# SVCSYNTH00.net
KiCad netlist of a schematic drawn in EAGLE
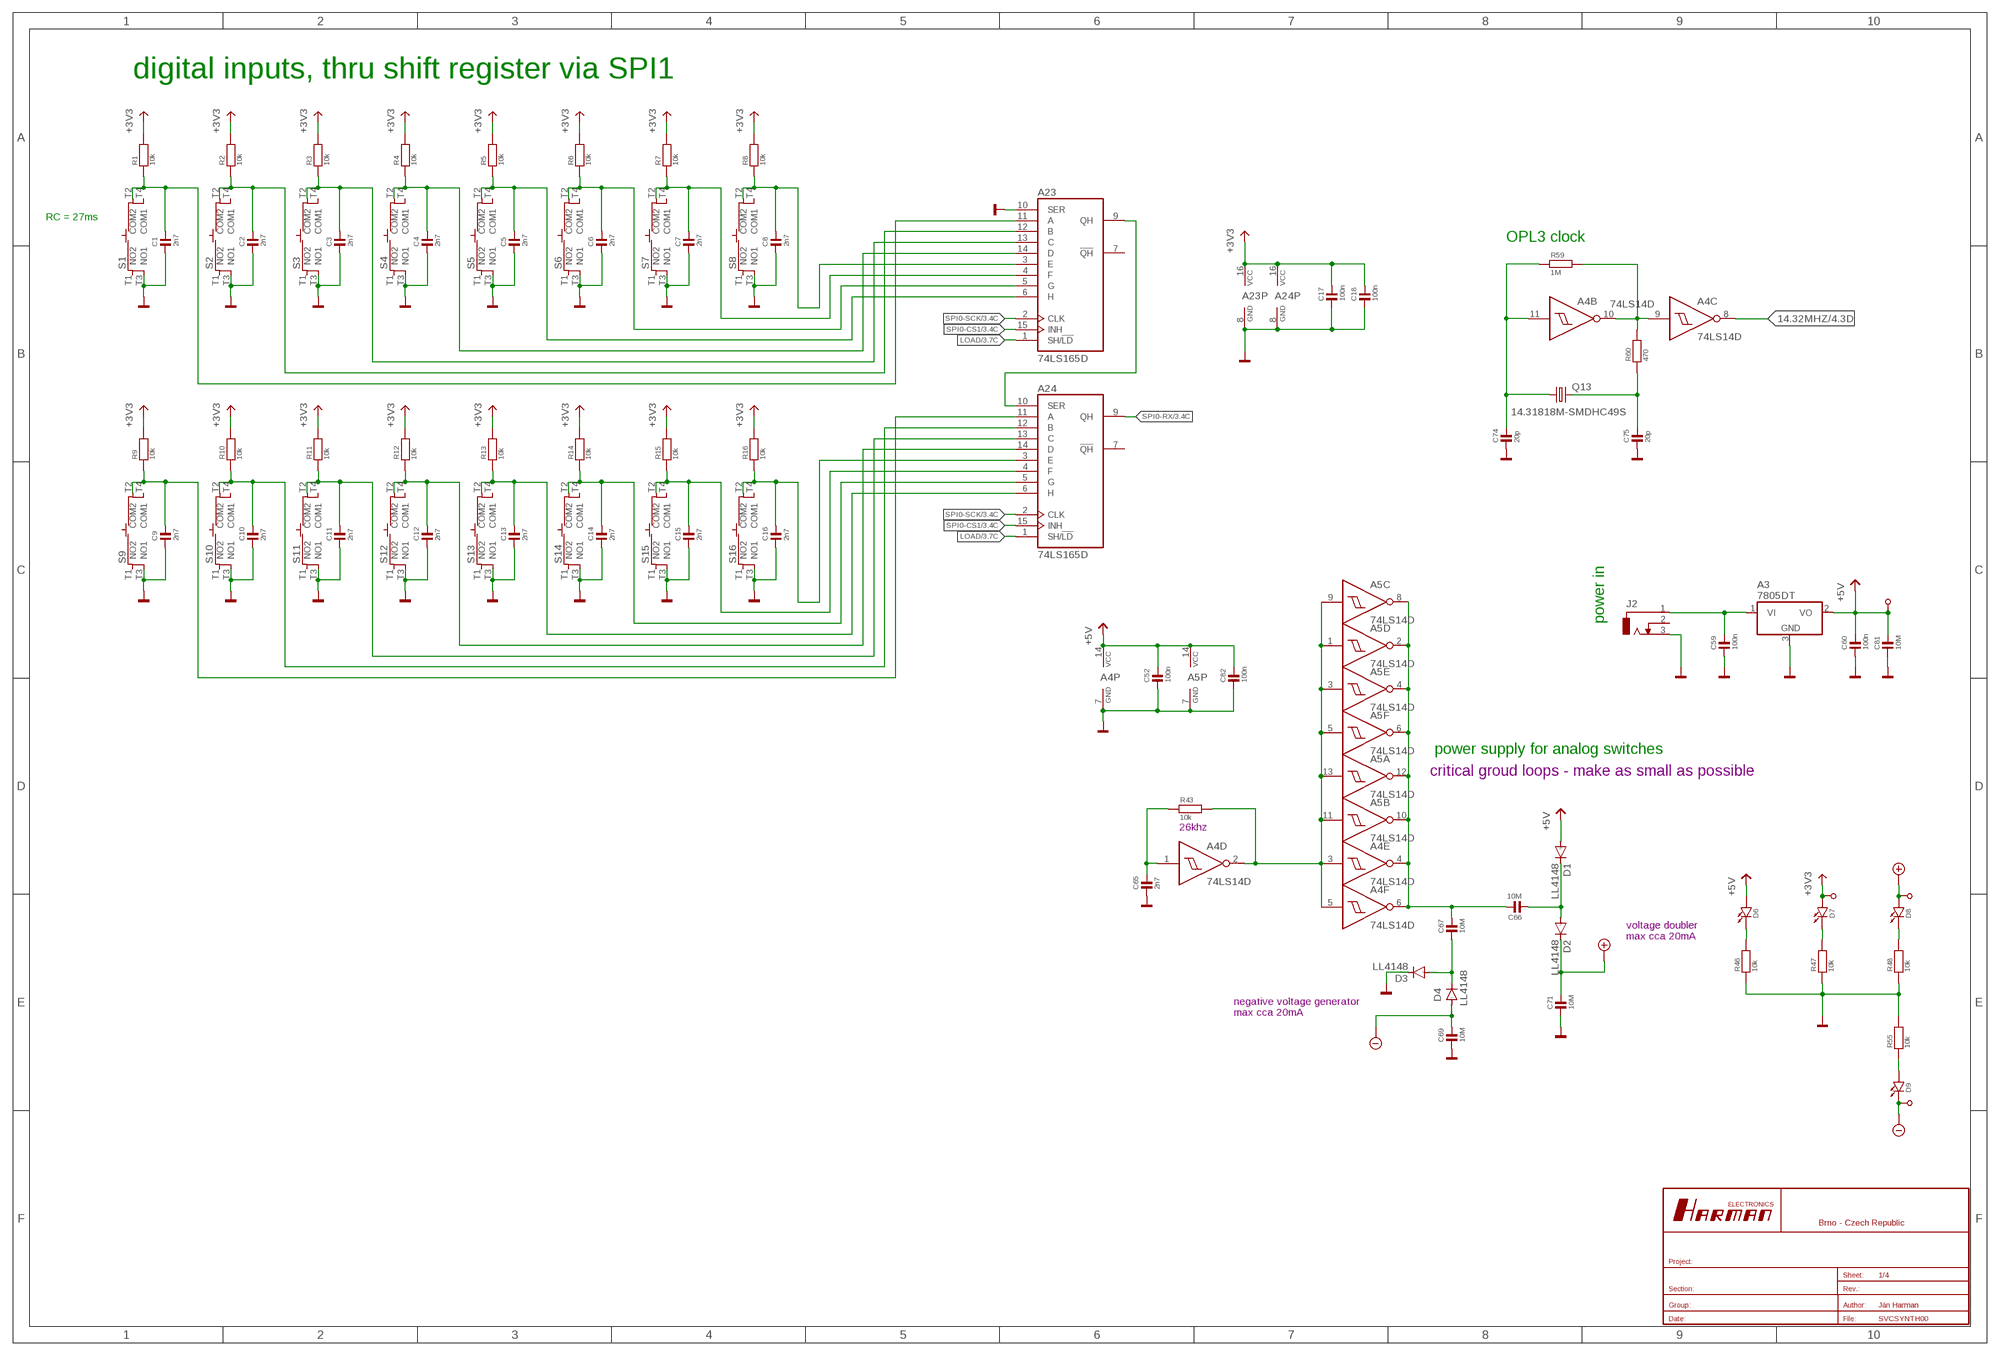
[diagram p0: schematic, sheet 1]
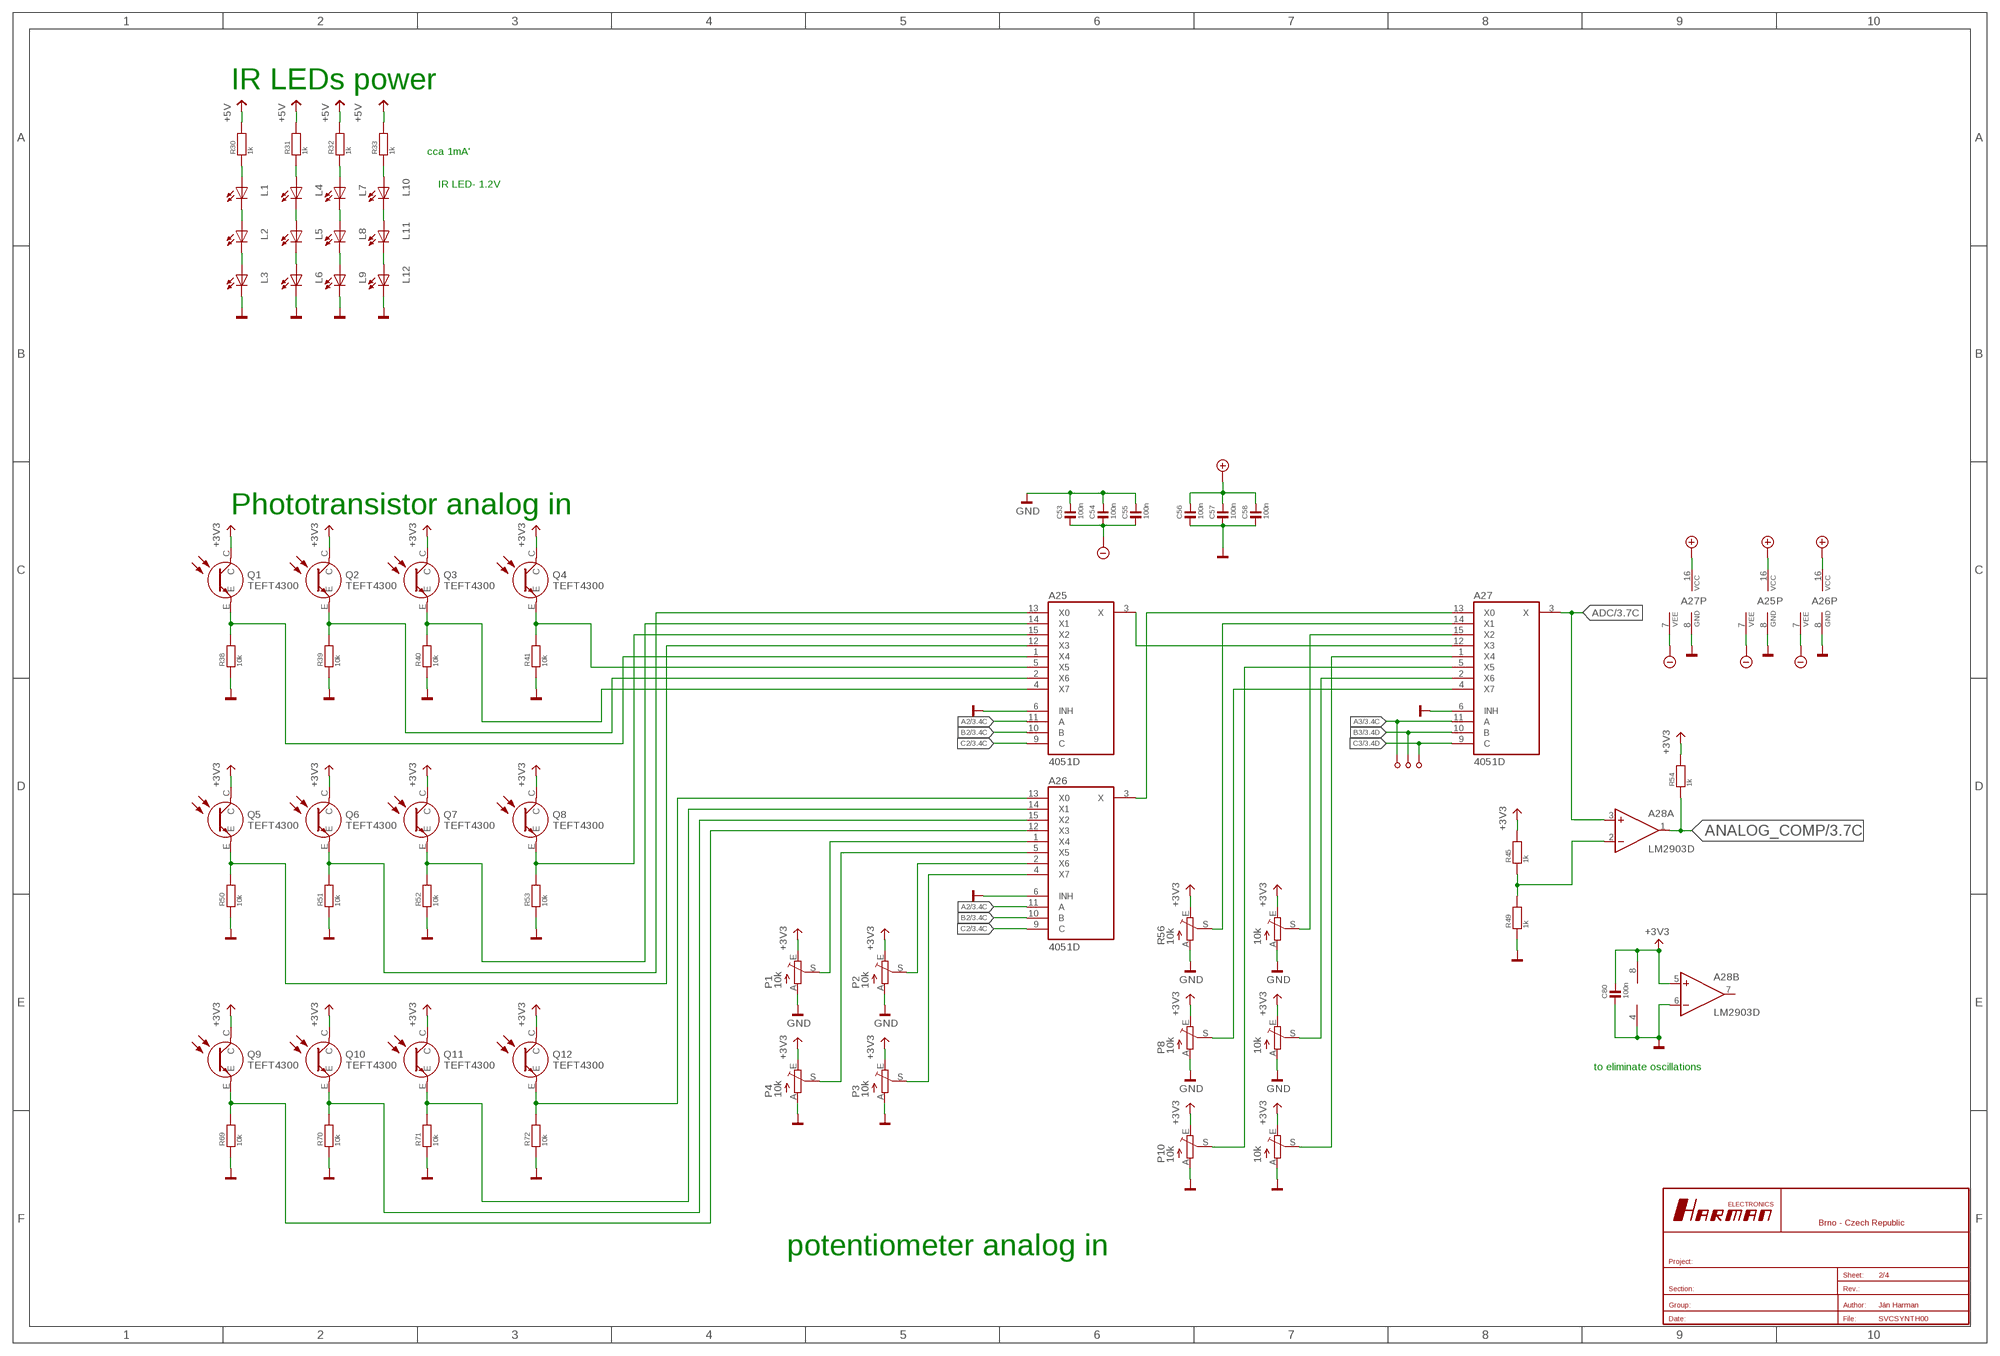
[diagram p1: schematic, sheet 2]
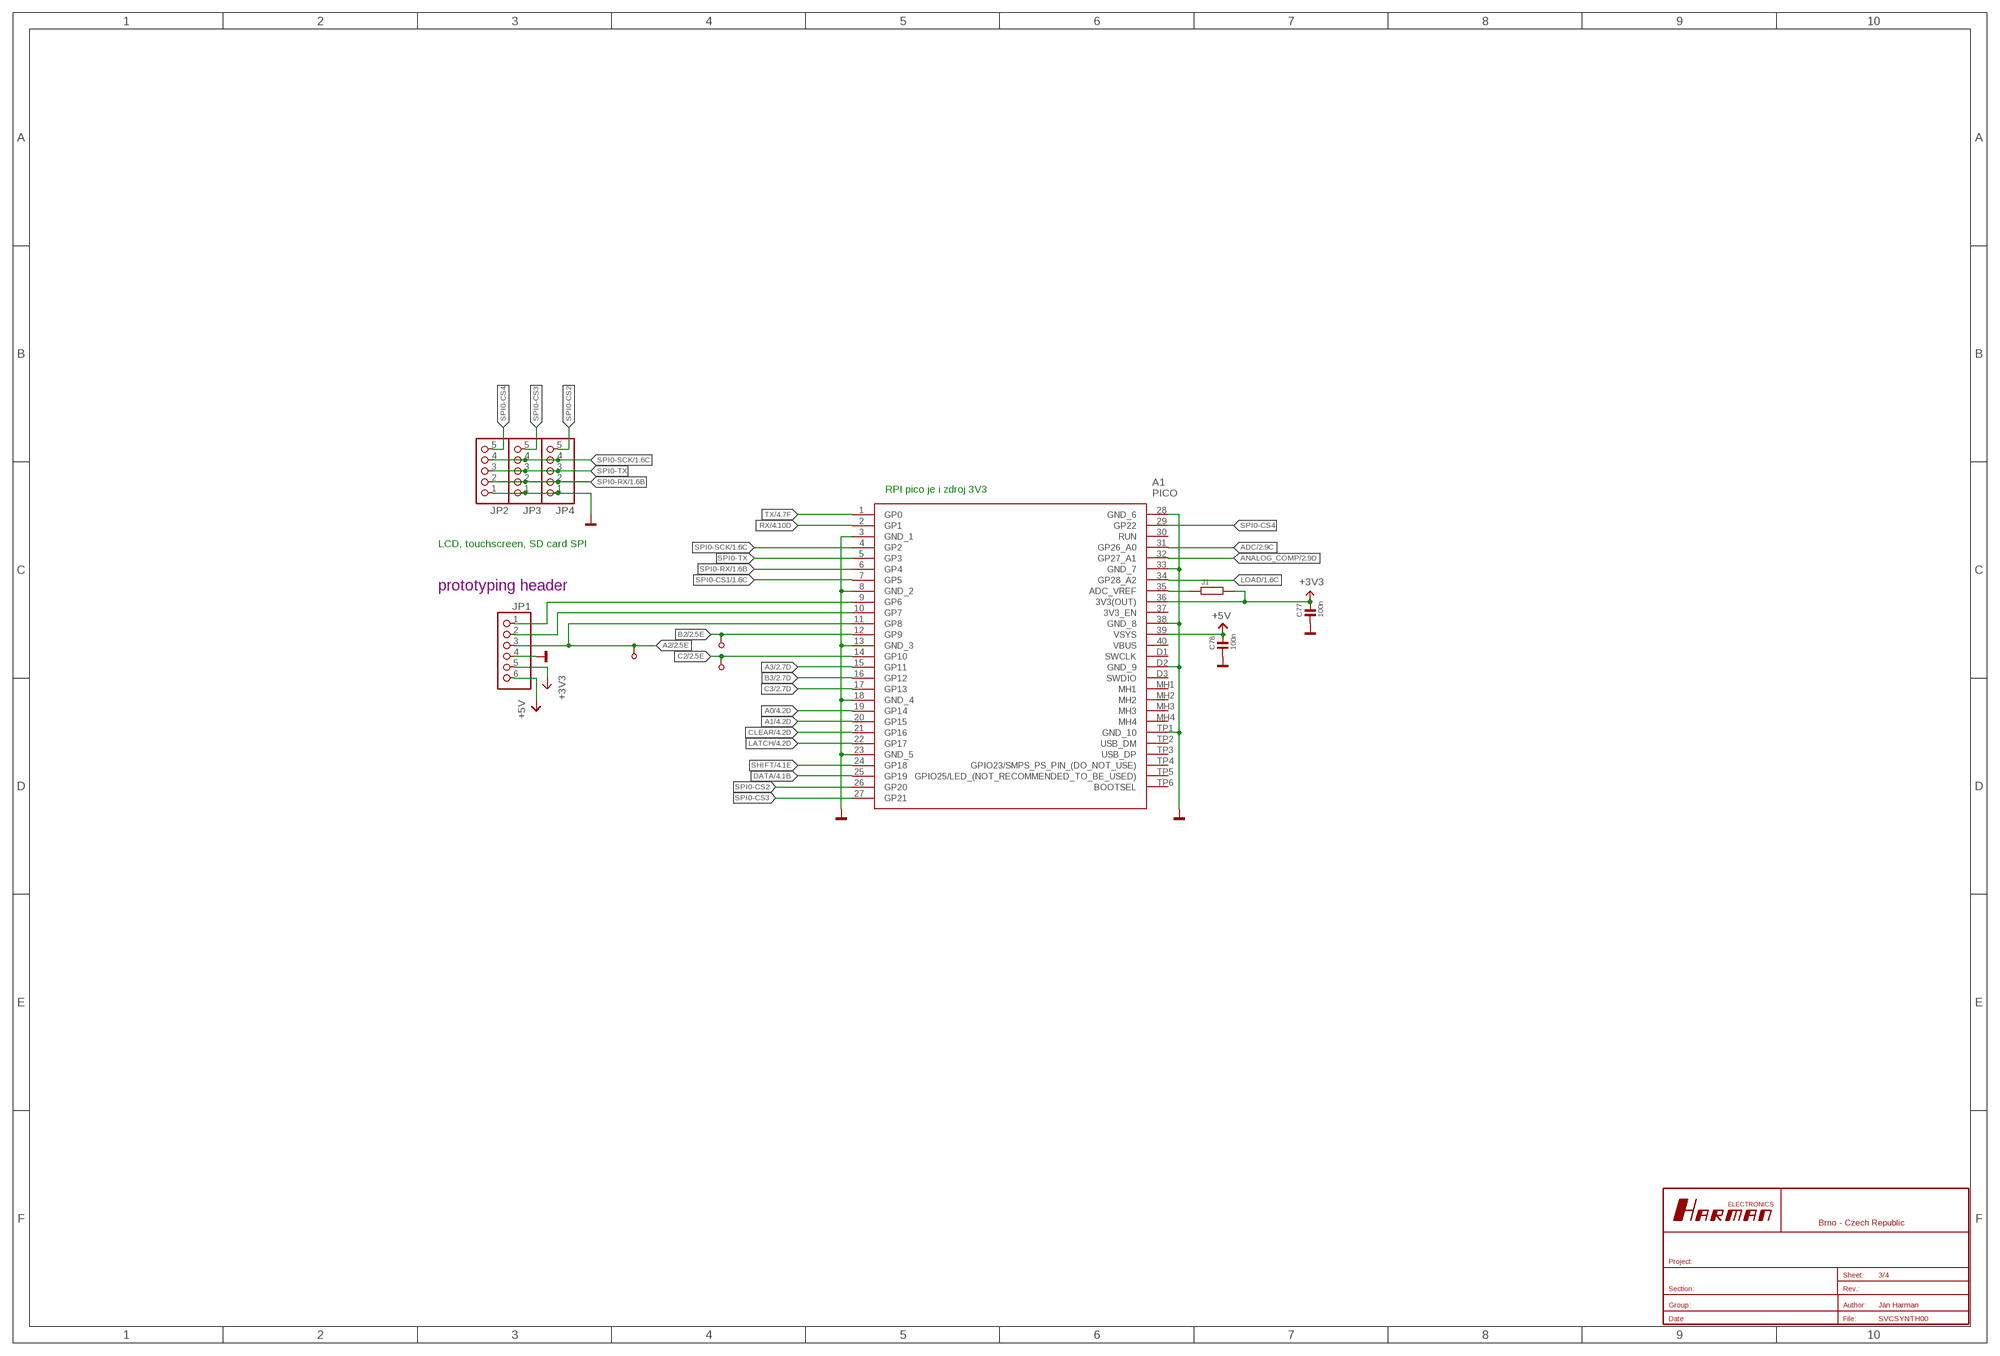
[diagram p2: schematic, sheet 3]
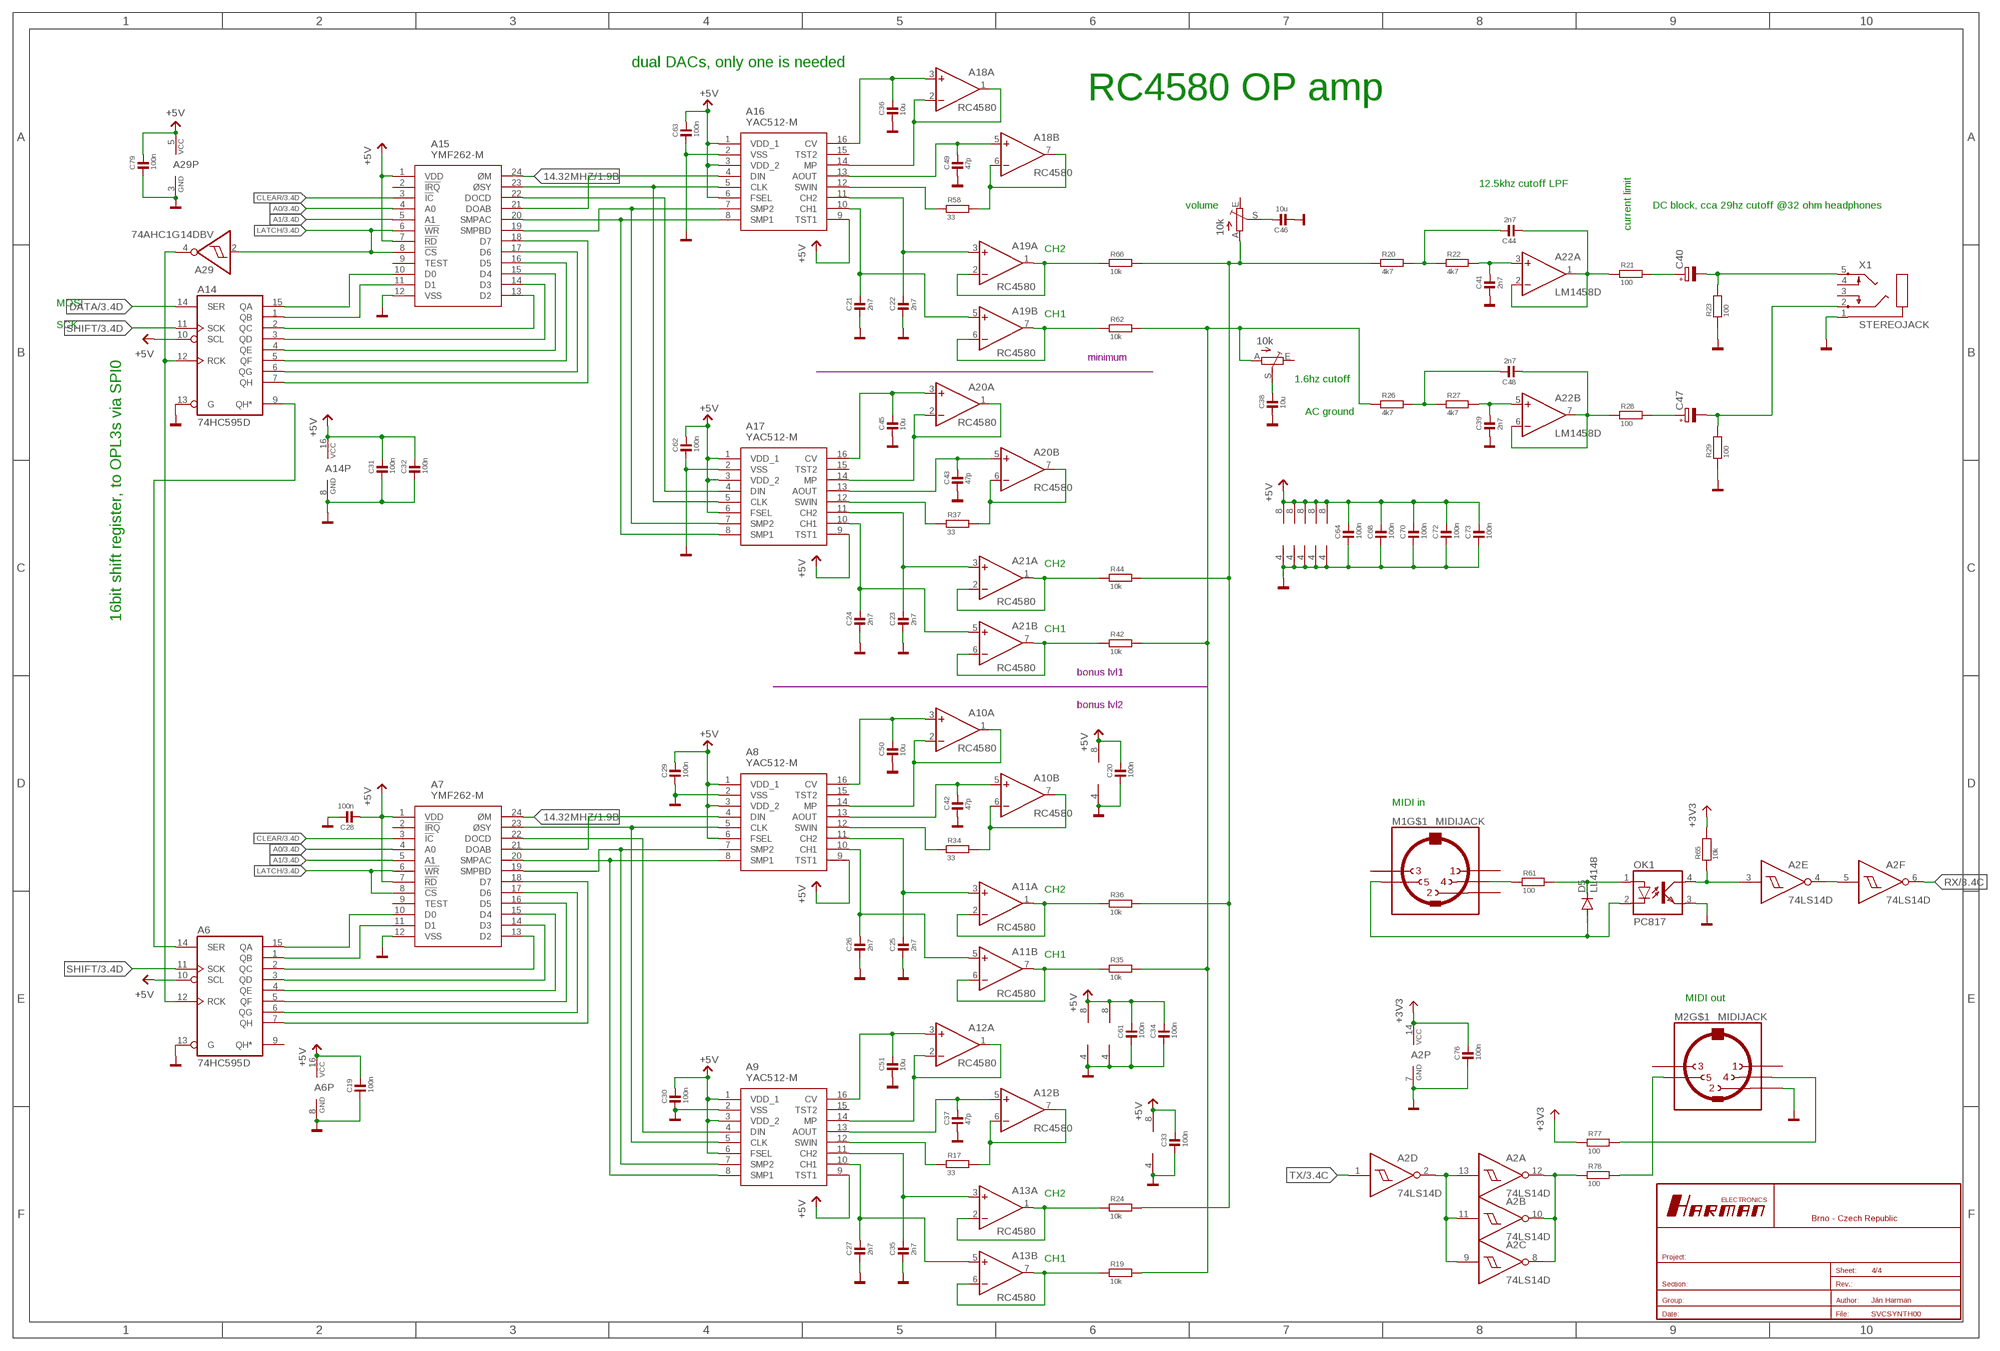
[diagram p3: schematic, sheet 4]

(export (version "E")
  (design (tool "Eeschema 10.0.6"))
  (components
    (comp (ref "A3")
      (value "7805DT")
      (footprint "eagle-import:TO252")
      (libsource (lib "eagle-import") (part "78DT05"))
    )
    (comp (ref "A4")
      (value "74LS14D")
      (footprint "eagle-import:SO14")
      (libsource (lib "eagle-import") (part "7414DLS"))
    )
    (comp (ref "A5")
      (value "74LS14D")
      (footprint "eagle-import:SO14")
      (libsource (lib "eagle-import") (part "7414DLS"))
    )
    (comp (ref "A23")
      (value "74LS165D")
      (footprint "eagle-import:SO16")
      (libsource (lib "eagle-import") (part "74165DLS"))
    )
    (comp (ref "A24")
      (value "74LS165D")
      (footprint "eagle-import:SO16")
      (libsource (lib "eagle-import") (part "74165DLS"))
    )
    (comp (ref "C1")
      (value "2n7")
      (footprint "eagle-import:R0805")
      (libsource (lib "eagle-import") (part "C0805"))
    )
    (comp (ref "C2")
      (value "2n7")
      (footprint "eagle-import:R0805")
      (libsource (lib "eagle-import") (part "C0805"))
    )
    (comp (ref "C3")
      (value "2n7")
      (footprint "eagle-import:R0805")
      (libsource (lib "eagle-import") (part "C0805"))
    )
    (comp (ref "C4")
      (value "2n7")
      (footprint "eagle-import:R0805")
      (libsource (lib "eagle-import") (part "C0805"))
    )
    (comp (ref "C5")
      (value "2n7")
      (footprint "eagle-import:R0805")
      (libsource (lib "eagle-import") (part "C0805"))
    )
    (comp (ref "C6")
      (value "2n7")
      (footprint "eagle-import:R0805")
      (libsource (lib "eagle-import") (part "C0805"))
    )
    (comp (ref "C7")
      (value "2n7")
      (footprint "eagle-import:R0805")
      (libsource (lib "eagle-import") (part "C0805"))
    )
    (comp (ref "C8")
      (value "2n7")
      (footprint "eagle-import:R0805")
      (libsource (lib "eagle-import") (part "C0805"))
    )
    (comp (ref "C9")
      (value "2n7")
      (footprint "eagle-import:R0805")
      (libsource (lib "eagle-import") (part "C0805"))
    )
    (comp (ref "C10")
      (value "2n7")
      (footprint "eagle-import:R0805")
      (libsource (lib "eagle-import") (part "C0805"))
    )
    (comp (ref "C11")
      (value "2n7")
      (footprint "eagle-import:R0805")
      (libsource (lib "eagle-import") (part "C0805"))
    )
    (comp (ref "C12")
      (value "2n7")
      (footprint "eagle-import:R0805")
      (libsource (lib "eagle-import") (part "C0805"))
    )
    (comp (ref "C13")
      (value "2n7")
      (footprint "eagle-import:R0805")
      (libsource (lib "eagle-import") (part "C0805"))
    )
    (comp (ref "C14")
      (value "2n7")
      (footprint "eagle-import:R0805")
      (libsource (lib "eagle-import") (part "C0805"))
    )
    (comp (ref "C15")
      (value "2n7")
      (footprint "eagle-import:R0805")
      (libsource (lib "eagle-import") (part "C0805"))
    )
    (comp (ref "C16")
      (value "2n7")
      (footprint "eagle-import:R0805")
      (libsource (lib "eagle-import") (part "C0805"))
    )
    (comp (ref "C17")
      (value "100n")
      (footprint "eagle-import:R0805")
      (libsource (lib "eagle-import") (part "C0805"))
    )
    (comp (ref "C18")
      (value "100n")
      (footprint "eagle-import:R0805")
      (libsource (lib "eagle-import") (part "C0805"))
    )
    (comp (ref "C52")
      (value "100n")
      (footprint "eagle-import:R0805")
      (libsource (lib "eagle-import") (part "C0805"))
    )
    (comp (ref "C59")
      (value "100n")
      (footprint "eagle-import:R0805")
      (libsource (lib "eagle-import") (part "C0805"))
    )
    (comp (ref "C60")
      (value "100n")
      (footprint "eagle-import:R0805")
      (libsource (lib "eagle-import") (part "C0805"))
    )
    (comp (ref "C65")
      (value "2n7")
      (footprint "eagle-import:R0805")
      (libsource (lib "eagle-import") (part "C0805"))
    )
    (comp (ref "C66")
      (value "10M")
      (footprint "eagle-import:R1206")
      (libsource (lib "eagle-import") (part "C1206"))
    )
    (comp (ref "C67")
      (value "10M")
      (footprint "eagle-import:R1206")
      (libsource (lib "eagle-import") (part "C1206"))
    )
    (comp (ref "C69")
      (value "10M")
      (footprint "eagle-import:R1206")
      (libsource (lib "eagle-import") (part "C1206"))
    )
    (comp (ref "C71")
      (value "10M")
      (footprint "eagle-import:R1206")
      (libsource (lib "eagle-import") (part "C1206"))
    )
    (comp (ref "C74")
      (value "20p")
      (footprint "eagle-import:R0805")
      (libsource (lib "eagle-import") (part "C0805"))
    )
    (comp (ref "C75")
      (value "20p")
      (footprint "eagle-import:R0805")
      (libsource (lib "eagle-import") (part "C0805"))
    )
    (comp (ref "C81")
      (value "10M")
      (footprint "eagle-import:R1206")
      (libsource (lib "eagle-import") (part "C1206"))
    )
    (comp (ref "C82")
      (value "100n")
      (footprint "eagle-import:R0805")
      (libsource (lib "eagle-import") (part "C0805"))
    )
    (comp (ref "D1")
      (value "LL4148")
      (footprint "eagle-import:SOD80C")
      (libsource (lib "eagle-import") (part "DIODE-SOD80C"))
    )
    (comp (ref "D2")
      (value "LL4148")
      (footprint "eagle-import:SOD80C")
      (libsource (lib "eagle-import") (part "DIODE-SOD80C"))
    )
    (comp (ref "D3")
      (value "LL4148")
      (footprint "eagle-import:SOD80C")
      (libsource (lib "eagle-import") (part "DIODE-SOD80C"))
    )
    (comp (ref "D4")
      (value "LL4148")
      (footprint "eagle-import:SOD80C")
      (libsource (lib "eagle-import") (part "DIODE-SOD80C"))
    )
    (comp (ref "D6")
      (value "LED3MM")
      (footprint "eagle-import:LED3MM")
      (libsource (lib "eagle-import") (part "LED3MM"))
    )
    (comp (ref "D7")
      (value "LED3MM")
      (footprint "eagle-import:LED3MM")
      (libsource (lib "eagle-import") (part "LED3MM"))
    )
    (comp (ref "D8")
      (value "LED3MM")
      (footprint "eagle-import:LED3MM")
      (libsource (lib "eagle-import") (part "LED3MM"))
    )
    (comp (ref "D9")
      (value "LED3MM")
      (footprint "eagle-import:LED3MM")
      (libsource (lib "eagle-import") (part "LED3MM"))
    )
    (comp (ref "J2")
      (value "DCJ0303")
      (footprint "eagle-import:DCJ0303")
      (libsource (lib "eagle-import") (part "DCJ0303"))
    )
    (comp (ref "K1")
      (value "K1_0.9_1.8")
      (footprint "eagle-import:K_0.9_1.8")
      (libsource (lib "eagle-import") (part "K1_0.9_1.8"))
    )
    (comp (ref "K2")
      (value "K1_0.9_1.8")
      (footprint "eagle-import:K_0.9_1.8")
      (libsource (lib "eagle-import") (part "K1_0.9_1.8"))
    )
    (comp (ref "K3")
      (value "K1_0.9_1.8")
      (footprint "eagle-import:K_0.9_1.8")
      (libsource (lib "eagle-import") (part "K1_0.9_1.8"))
    )
    (comp (ref "K4")
      (value "K1_0.9_1.8")
      (footprint "eagle-import:K_0.9_1.8")
      (libsource (lib "eagle-import") (part "K1_0.9_1.8"))
    )
    (comp (ref "Q13")
      (value "14.31818M-SMDHC49S")
      (footprint "eagle-import:CSM-7X-DU")
      (libsource (lib "eagle-import") (part "CSM-7X-DU"))
    )
    (comp (ref "R1")
      (value "10k")
      (footprint "eagle-import:R0805")
      (libsource (lib "eagle-import") (part "R0805"))
    )
    (comp (ref "R2")
      (value "10k")
      (footprint "eagle-import:R0805")
      (libsource (lib "eagle-import") (part "R0805"))
    )
    (comp (ref "R3")
      (value "10k")
      (footprint "eagle-import:R0805")
      (libsource (lib "eagle-import") (part "R0805"))
    )
    (comp (ref "R4")
      (value "10k")
      (footprint "eagle-import:R0805")
      (libsource (lib "eagle-import") (part "R0805"))
    )
    (comp (ref "R5")
      (value "10k")
      (footprint "eagle-import:R0805")
      (libsource (lib "eagle-import") (part "R0805"))
    )
    (comp (ref "R6")
      (value "10k")
      (footprint "eagle-import:R0805")
      (libsource (lib "eagle-import") (part "R0805"))
    )
    (comp (ref "R7")
      (value "10k")
      (footprint "eagle-import:R0805")
      (libsource (lib "eagle-import") (part "R0805"))
    )
    (comp (ref "R8")
      (value "10k")
      (footprint "eagle-import:R0805")
      (libsource (lib "eagle-import") (part "R0805"))
    )
    (comp (ref "R9")
      (value "10k")
      (footprint "eagle-import:R0805")
      (libsource (lib "eagle-import") (part "R0805"))
    )
    (comp (ref "R10")
      (value "10k")
      (footprint "eagle-import:R0805")
      (libsource (lib "eagle-import") (part "R0805"))
    )
    (comp (ref "R11")
      (value "10k")
      (footprint "eagle-import:R0805")
      (libsource (lib "eagle-import") (part "R0805"))
    )
    (comp (ref "R12")
      (value "10k")
      (footprint "eagle-import:R0805")
      (libsource (lib "eagle-import") (part "R0805"))
    )
    (comp (ref "R13")
      (value "10k")
      (footprint "eagle-import:R0805")
      (libsource (lib "eagle-import") (part "R0805"))
    )
    (comp (ref "R14")
      (value "10k")
      (footprint "eagle-import:R0805")
      (libsource (lib "eagle-import") (part "R0805"))
    )
    (comp (ref "R15")
      (value "10k")
      (footprint "eagle-import:R0805")
      (libsource (lib "eagle-import") (part "R0805"))
    )
    (comp (ref "R16")
      (value "10k")
      (footprint "eagle-import:R0805")
      (libsource (lib "eagle-import") (part "R0805"))
    )
    (comp (ref "R43")
      (value "10k")
      (footprint "eagle-import:R0805")
      (libsource (lib "eagle-import") (part "R0805"))
    )
    (comp (ref "R46")
      (value "10k")
      (footprint "eagle-import:R0805")
      (libsource (lib "eagle-import") (part "R0805"))
    )
    (comp (ref "R47")
      (value "10k")
      (footprint "eagle-import:R0805")
      (libsource (lib "eagle-import") (part "R0805"))
    )
    (comp (ref "R48")
      (value "10k")
      (footprint "eagle-import:R0805")
      (libsource (lib "eagle-import") (part "R0805"))
    )
    (comp (ref "R55")
      (value "10k")
      (footprint "eagle-import:R0805")
      (libsource (lib "eagle-import") (part "R0805"))
    )
    (comp (ref "R59")
      (value "1M")
      (footprint "eagle-import:R0805")
      (libsource (lib "eagle-import") (part "R0805"))
    )
    (comp (ref "R60")
      (value "470")
      (footprint "eagle-import:R0805")
      (libsource (lib "eagle-import") (part "R0805"))
    )
    (comp (ref "S1")
      (value "101-TS6211T1603-EV")
      (footprint "eagle-import:101TS6211T1603EV")
      (libsource (lib "eagle-import") (part "101-TS6211T1603-EV"))
    )
    (comp (ref "S2")
      (value "101-TS6211T1603-EV")
      (footprint "eagle-import:101TS6211T1603EV")
      (libsource (lib "eagle-import") (part "101-TS6211T1603-EV"))
    )
    (comp (ref "S3")
      (value "101-TS6211T1603-EV")
      (footprint "eagle-import:101TS6211T1603EV")
      (libsource (lib "eagle-import") (part "101-TS6211T1603-EV"))
    )
    (comp (ref "S4")
      (value "101-TS6211T1603-EV")
      (footprint "eagle-import:101TS6211T1603EV")
      (libsource (lib "eagle-import") (part "101-TS6211T1603-EV"))
    )
    (comp (ref "S5")
      (value "101-TS6211T1603-EV")
      (footprint "eagle-import:101TS6211T1603EV")
      (libsource (lib "eagle-import") (part "101-TS6211T1603-EV"))
    )
    (comp (ref "S6")
      (value "101-TS6211T1603-EV")
      (footprint "eagle-import:101TS6211T1603EV")
      (libsource (lib "eagle-import") (part "101-TS6211T1603-EV"))
    )
    (comp (ref "S7")
      (value "101-TS6211T1603-EV")
      (footprint "eagle-import:101TS6211T1603EV")
      (libsource (lib "eagle-import") (part "101-TS6211T1603-EV"))
    )
    (comp (ref "S8")
      (value "101-TS6211T1603-EV")
      (footprint "eagle-import:101TS6211T1603EV")
      (libsource (lib "eagle-import") (part "101-TS6211T1603-EV"))
    )
    (comp (ref "S9")
      (value "101-TS6211T1603-EV")
      (footprint "eagle-import:101TS6211T1603EV")
      (libsource (lib "eagle-import") (part "101-TS6211T1603-EV"))
    )
    (comp (ref "S10")
      (value "101-TS6211T1603-EV")
      (footprint "eagle-import:101TS6211T1603EV")
      (libsource (lib "eagle-import") (part "101-TS6211T1603-EV"))
    )
    (comp (ref "S11")
      (value "101-TS6211T1603-EV")
      (footprint "eagle-import:101TS6211T1603EV")
      (libsource (lib "eagle-import") (part "101-TS6211T1603-EV"))
    )
    (comp (ref "S12")
      (value "101-TS6211T1603-EV")
      (footprint "eagle-import:101TS6211T1603EV")
      (libsource (lib "eagle-import") (part "101-TS6211T1603-EV"))
    )
    (comp (ref "S13")
      (value "101-TS6211T1603-EV")
      (footprint "eagle-import:101TS6211T1603EV")
      (libsource (lib "eagle-import") (part "101-TS6211T1603-EV"))
    )
    (comp (ref "S14")
      (value "101-TS6211T1603-EV")
      (footprint "eagle-import:101TS6211T1603EV")
      (libsource (lib "eagle-import") (part "101-TS6211T1603-EV"))
    )
    (comp (ref "S15")
      (value "101-TS6211T1603-EV")
      (footprint "eagle-import:101TS6211T1603EV")
      (libsource (lib "eagle-import") (part "101-TS6211T1603-EV"))
    )
    (comp (ref "S16")
      (value "101-TS6211T1603-EV")
      (footprint "eagle-import:101TS6211T1603EV")
      (libsource (lib "eagle-import") (part "101-TS6211T1603-EV"))
    )
    (comp (ref "A1")
      (value "PICO")
      (footprint "eagle-import:PICO")
      (libsource (lib "eagle-import") (part "PICO"))
    )
    (comp (ref "C77")
      (value "100n")
      (footprint "eagle-import:R0805")
      (libsource (lib "eagle-import") (part "C0805"))
    )
    (comp (ref "C78")
      (value "100n")
      (footprint "eagle-import:R0805")
      (libsource (lib "eagle-import") (part "C0805"))
    )
    (comp (ref "J1")
      (value "R0402")
      (footprint "eagle-import:R0402")
      (libsource (lib "eagle-import") (part "R0402"))
    )
    (comp (ref "JP1")
      (value "PINHD-1X6")
      (footprint "eagle-import:1X06")
      (libsource (lib "eagle-import") (part "PINHD-1X6"))
    )
    (comp (ref "JP2")
      (value "PINHD-1X5")
      (footprint "eagle-import:1X05")
      (libsource (lib "eagle-import") (part "PINHD-1X5"))
    )
    (comp (ref "JP3")
      (value "PINHD-1X5")
      (footprint "eagle-import:1X05")
      (libsource (lib "eagle-import") (part "PINHD-1X5"))
    )
    (comp (ref "JP4")
      (value "PINHD-1X5")
      (footprint "eagle-import:1X05")
      (libsource (lib "eagle-import") (part "PINHD-1X5"))
    )
    (comp (ref "K5")
      (value "K1_1.0_2.2")
      (footprint "eagle-import:K_1.0_2.2")
      (libsource (lib "eagle-import") (part "K1_1.0_2.2"))
    )
    (comp (ref "K6")
      (value "K1_1.0_2.2")
      (footprint "eagle-import:K_1.0_2.2")
      (libsource (lib "eagle-import") (part "K1_1.0_2.2"))
    )
    (comp (ref "K7")
      (value "K1_1.0_2.2")
      (footprint "eagle-import:K_1.0_2.2")
      (libsource (lib "eagle-import") (part "K1_1.0_2.2"))
    )
    (comp (ref "A25")
      (value "4051D")
      (footprint "eagle-import:SO16")
      (libsource (lib "eagle-import") (part "4051D"))
    )
    (comp (ref "A26")
      (value "4051D")
      (footprint "eagle-import:SO16")
      (libsource (lib "eagle-import") (part "4051D"))
    )
    (comp (ref "A27")
      (value "4051D")
      (footprint "eagle-import:SO16")
      (libsource (lib "eagle-import") (part "4051D"))
    )
    (comp (ref "A28")
      (value "LM2903D")
      (footprint "eagle-import:SO08")
      (libsource (lib "eagle-import") (part "LM2903D"))
    )
    (comp (ref "C53")
      (value "100n")
      (footprint "eagle-import:R0805")
      (libsource (lib "eagle-import") (part "C0805"))
    )
    (comp (ref "C54")
      (value "100n")
      (footprint "eagle-import:R0805")
      (libsource (lib "eagle-import") (part "C0805"))
    )
    (comp (ref "C55")
      (value "100n")
      (footprint "eagle-import:R0805")
      (libsource (lib "eagle-import") (part "C0805"))
    )
    (comp (ref "C56")
      (value "100n")
      (footprint "eagle-import:R0805")
      (libsource (lib "eagle-import") (part "C0805"))
    )
    (comp (ref "C57")
      (value "100n")
      (footprint "eagle-import:R0805")
      (libsource (lib "eagle-import") (part "C0805"))
    )
    (comp (ref "C58")
      (value "100n")
      (footprint "eagle-import:R0805")
      (libsource (lib "eagle-import") (part "C0805"))
    )
    (comp (ref "C80")
      (value "100n")
      (footprint "eagle-import:R0805")
      (libsource (lib "eagle-import") (part "C0805"))
    )
    (comp (ref "K8")
      (value "K1_0.8_1.6")
      (footprint "eagle-import:K_0.8_1.6")
      (libsource (lib "eagle-import") (part "K1_0.8_1.6"))
    )
    (comp (ref "K9")
      (value "K1_0.8_1.6")
      (footprint "eagle-import:K_0.8_1.6")
      (libsource (lib "eagle-import") (part "K1_0.8_1.6"))
    )
    (comp (ref "K10")
      (value "K1_0.8_1.6")
      (footprint "eagle-import:K_0.8_1.6")
      (libsource (lib "eagle-import") (part "K1_0.8_1.6"))
    )
    (comp (ref "L1")
      (value "LED3MM")
      (footprint "eagle-import:LED3MM")
      (libsource (lib "eagle-import") (part "adafruit_LED3MM"))
    )
    (comp (ref "L2")
      (value "LED3MM")
      (footprint "eagle-import:LED3MM")
      (libsource (lib "eagle-import") (part "adafruit_LED3MM"))
    )
    (comp (ref "L3")
      (value "LED3MM")
      (footprint "eagle-import:LED3MM")
      (libsource (lib "eagle-import") (part "adafruit_LED3MM"))
    )
    (comp (ref "L4")
      (value "LED3MM")
      (footprint "eagle-import:LED3MM")
      (libsource (lib "eagle-import") (part "adafruit_LED3MM"))
    )
    (comp (ref "L5")
      (value "LED3MM")
      (footprint "eagle-import:LED3MM")
      (libsource (lib "eagle-import") (part "adafruit_LED3MM"))
    )
    (comp (ref "L6")
      (value "LED3MM")
      (footprint "eagle-import:LED3MM")
      (libsource (lib "eagle-import") (part "adafruit_LED3MM"))
    )
    (comp (ref "L7")
      (value "LED3MM")
      (footprint "eagle-import:LED3MM")
      (libsource (lib "eagle-import") (part "adafruit_LED3MM"))
    )
    (comp (ref "L8")
      (value "LED3MM")
      (footprint "eagle-import:LED3MM")
      (libsource (lib "eagle-import") (part "adafruit_LED3MM"))
    )
    (comp (ref "L9")
      (value "LED3MM")
      (footprint "eagle-import:LED3MM")
      (libsource (lib "eagle-import") (part "adafruit_LED3MM"))
    )
    (comp (ref "L10")
      (value "LED3MM")
      (footprint "eagle-import:LED3MM")
      (libsource (lib "eagle-import") (part "adafruit_LED3MM"))
    )
    (comp (ref "L11")
      (value "LED3MM")
      (footprint "eagle-import:LED3MM")
      (libsource (lib "eagle-import") (part "adafruit_LED3MM"))
    )
    (comp (ref "L12")
      (value "LED3MM")
      (footprint "eagle-import:LED3MM")
      (libsource (lib "eagle-import") (part "adafruit_LED3MM"))
    )
    (comp (ref "P1")
      (value "10k")
      (footprint "eagle-import:CA6V")
      (libsource (lib "eagle-import") (part "TRIM_EU-CA6V"))
    )
    (comp (ref "P2")
      (value "10k")
      (footprint "eagle-import:CA6V")
      (libsource (lib "eagle-import") (part "TRIM_EU-CA6V"))
    )
    (comp (ref "P3")
      (value "10k")
      (footprint "eagle-import:CA6V")
      (libsource (lib "eagle-import") (part "TRIM_EU-CA6V"))
    )
    (comp (ref "P4")
      (value "10k")
      (footprint "eagle-import:CA6V")
      (libsource (lib "eagle-import") (part "TRIM_EU-CA6V"))
    )
    (comp (ref "P6")
      (value "10k")
      (footprint "eagle-import:CA6V")
      (libsource (lib "eagle-import") (part "TRIM_EU-CA6V"))
    )
    (comp (ref "P8")
      (value "10k")
      (footprint "eagle-import:CA6V")
      (libsource (lib "eagle-import") (part "TRIM_EU-CA6V"))
    )
    (comp (ref "P10")
      (value "10k")
      (footprint "eagle-import:CA6V")
      (libsource (lib "eagle-import") (part "TRIM_EU-CA6V"))
    )
    (comp (ref "Q1")
      (value "TEFT4300")
      (footprint "eagle-import:TEFT4300")
      (fields (field (name "MOUSER_PART_NUMBER") "782-TEFT4300"))
      (libsource (lib "eagle-import") (part "TEFT4300"))
    )
    (comp (ref "Q2")
      (value "TEFT4300")
      (footprint "eagle-import:TEFT4300")
      (fields (field (name "MOUSER_PART_NUMBER") "782-TEFT4300"))
      (libsource (lib "eagle-import") (part "TEFT4300"))
    )
    (comp (ref "Q3")
      (value "TEFT4300")
      (footprint "eagle-import:TEFT4300")
      (fields (field (name "MOUSER_PART_NUMBER") "782-TEFT4300"))
      (libsource (lib "eagle-import") (part "TEFT4300"))
    )
    (comp (ref "Q4")
      (value "TEFT4300")
      (footprint "eagle-import:TEFT4300")
      (fields (field (name "MOUSER_PART_NUMBER") "782-TEFT4300"))
      (libsource (lib "eagle-import") (part "TEFT4300"))
    )
    (comp (ref "Q5")
      (value "TEFT4300")
      (footprint "eagle-import:TEFT4300")
      (fields (field (name "MOUSER_PART_NUMBER") "782-TEFT4300"))
      (libsource (lib "eagle-import") (part "TEFT4300"))
    )
    (comp (ref "Q6")
      (value "TEFT4300")
      (footprint "eagle-import:TEFT4300")
      (fields (field (name "MOUSER_PART_NUMBER") "782-TEFT4300"))
      (libsource (lib "eagle-import") (part "TEFT4300"))
    )
    (comp (ref "Q7")
      (value "TEFT4300")
      (footprint "eagle-import:TEFT4300")
      (fields (field (name "MOUSER_PART_NUMBER") "782-TEFT4300"))
      (libsource (lib "eagle-import") (part "TEFT4300"))
    )
    (comp (ref "Q8")
      (value "TEFT4300")
      (footprint "eagle-import:TEFT4300")
      (fields (field (name "MOUSER_PART_NUMBER") "782-TEFT4300"))
      (libsource (lib "eagle-import") (part "TEFT4300"))
    )
    (comp (ref "Q9")
      (value "TEFT4300")
      (footprint "eagle-import:TEFT4300")
      (fields (field (name "MOUSER_PART_NUMBER") "782-TEFT4300"))
      (libsource (lib "eagle-import") (part "TEFT4300"))
    )
    (comp (ref "Q10")
      (value "TEFT4300")
      (footprint "eagle-import:TEFT4300")
      (fields (field (name "MOUSER_PART_NUMBER") "782-TEFT4300"))
      (libsource (lib "eagle-import") (part "TEFT4300"))
    )
    (comp (ref "Q11")
      (value "TEFT4300")
      (footprint "eagle-import:TEFT4300")
      (fields (field (name "MOUSER_PART_NUMBER") "782-TEFT4300"))
      (libsource (lib "eagle-import") (part "TEFT4300"))
    )
    (comp (ref "Q12")
      (value "TEFT4300")
      (footprint "eagle-import:TEFT4300")
      (fields (field (name "MOUSER_PART_NUMBER") "782-TEFT4300"))
      (libsource (lib "eagle-import") (part "TEFT4300"))
    )
    (comp (ref "R30")
      (value "1k")
      (footprint "eagle-import:R0805")
      (libsource (lib "eagle-import") (part "R0805"))
    )
    (comp (ref "R31")
      (value "1k")
      (footprint "eagle-import:R0805")
      (libsource (lib "eagle-import") (part "R0805"))
    )
    (comp (ref "R32")
      (value "1k")
      (footprint "eagle-import:R0805")
      (libsource (lib "eagle-import") (part "R0805"))
    )
    (comp (ref "R33")
      (value "1k")
      (footprint "eagle-import:R0805")
      (libsource (lib "eagle-import") (part "R0805"))
    )
    (comp (ref "R38")
      (value "10k")
      (footprint "eagle-import:R0805")
      (libsource (lib "eagle-import") (part "R0805"))
    )
    (comp (ref "R39")
      (value "10k")
      (footprint "eagle-import:R0805")
      (libsource (lib "eagle-import") (part "R0805"))
    )
    (comp (ref "R40")
      (value "10k")
      (footprint "eagle-import:R0805")
      (libsource (lib "eagle-import") (part "R0805"))
    )
    (comp (ref "R41")
      (value "10k")
      (footprint "eagle-import:R0805")
      (libsource (lib "eagle-import") (part "R0805"))
    )
    (comp (ref "R45")
      (value "1k")
      (footprint "eagle-import:R0805")
      (libsource (lib "eagle-import") (part "R0805"))
    )
    (comp (ref "R49")
      (value "1k")
      (footprint "eagle-import:R0805")
      (libsource (lib "eagle-import") (part "R0805"))
    )
    (comp (ref "R50")
      (value "10k")
      (footprint "eagle-import:R0805")
      (libsource (lib "eagle-import") (part "R0805"))
    )
    (comp (ref "R51")
      (value "10k")
      (footprint "eagle-import:R0805")
      (libsource (lib "eagle-import") (part "R0805"))
    )
    (comp (ref "R52")
      (value "10k")
      (footprint "eagle-import:R0805")
      (libsource (lib "eagle-import") (part "R0805"))
    )
    (comp (ref "R53")
      (value "10k")
      (footprint "eagle-import:R0805")
      (libsource (lib "eagle-import") (part "R0805"))
    )
    (comp (ref "R54")
      (value "1k")
      (footprint "eagle-import:R0805")
      (libsource (lib "eagle-import") (part "R0805"))
    )
    (comp (ref "R56")
      (value "10k")
      (footprint "eagle-import:CA6V")
      (libsource (lib "eagle-import") (part "TRIM_EU-CA6V"))
    )
    (comp (ref "R57")
      (value "10k")
      (footprint "eagle-import:CA6V")
      (libsource (lib "eagle-import") (part "TRIM_EU-CA6V"))
    )
    (comp (ref "R69")
      (value "10k")
      (footprint "eagle-import:R0805")
      (libsource (lib "eagle-import") (part "R0805"))
    )
    (comp (ref "R70")
      (value "10k")
      (footprint "eagle-import:R0805")
      (libsource (lib "eagle-import") (part "R0805"))
    )
    (comp (ref "R71")
      (value "10k")
      (footprint "eagle-import:R0805")
      (libsource (lib "eagle-import") (part "R0805"))
    )
    (comp (ref "R72")
      (value "10k")
      (footprint "eagle-import:R0805")
      (libsource (lib "eagle-import") (part "R0805"))
    )
    (comp (ref "R74")
      (value "10k")
      (footprint "eagle-import:CA6V")
      (libsource (lib "eagle-import") (part "TRIM_EU-CA6V"))
    )
    (comp (ref "A2")
      (value "74LS14D")
      (footprint "eagle-import:SO14")
      (libsource (lib "eagle-import") (part "7414DLS"))
    )
    (comp (ref "A6")
      (value "74HC595D")
      (footprint "eagle-import:SO16")
      (libsource (lib "eagle-import") (part "74595DHC"))
    )
    (comp (ref "A7")
      (value "YMF262-M")
      (footprint "eagle-import:SOIC127P1180X250-24N")
      (libsource (lib "eagle-import") (part "YMF262-M"))
    )
    (comp (ref "A8")
      (value "YAC512-M")
      (footprint "eagle-import:SOIC127P780X230-16N")
      (libsource (lib "eagle-import") (part "YAC512-M"))
    )
    (comp (ref "A9")
      (value "YAC512-M")
      (footprint "eagle-import:SOIC127P780X230-16N")
      (libsource (lib "eagle-import") (part "YAC512-M"))
    )
    (comp (ref "A10")
      (value "RC4580")
      (footprint "eagle-import:SO08")
      (libsource (lib "eagle-import") (part "1458DLM"))
    )
    (comp (ref "A11")
      (value "RC4580")
      (footprint "eagle-import:SO08")
      (libsource (lib "eagle-import") (part "1458DLM"))
    )
    (comp (ref "A12")
      (value "RC4580")
      (footprint "eagle-import:SO08")
      (libsource (lib "eagle-import") (part "1458DLM"))
    )
    (comp (ref "A13")
      (value "RC4580")
      (footprint "eagle-import:SO08")
      (libsource (lib "eagle-import") (part "1458DLM"))
    )
    (comp (ref "A14")
      (value "74HC595D")
      (footprint "eagle-import:SO16")
      (libsource (lib "eagle-import") (part "74595DHC"))
    )
    (comp (ref "A15")
      (value "YMF262-M")
      (footprint "eagle-import:SOIC127P1180X250-24N")
      (libsource (lib "eagle-import") (part "YMF262-M"))
    )
    (comp (ref "A16")
      (value "YAC512-M")
      (footprint "eagle-import:SOIC127P780X230-16N")
      (libsource (lib "eagle-import") (part "YAC512-M"))
    )
    (comp (ref "A17")
      (value "YAC512-M")
      (footprint "eagle-import:SOIC127P780X230-16N")
      (libsource (lib "eagle-import") (part "YAC512-M"))
    )
    (comp (ref "A18")
      (value "RC4580")
      (footprint "eagle-import:SO08")
      (libsource (lib "eagle-import") (part "1458DLM"))
    )
    (comp (ref "A19")
      (value "RC4580")
      (footprint "eagle-import:SO08")
      (libsource (lib "eagle-import") (part "1458DLM"))
    )
    (comp (ref "A20")
      (value "RC4580")
      (footprint "eagle-import:SO08")
      (libsource (lib "eagle-import") (part "1458DLM"))
    )
    (comp (ref "A21")
      (value "RC4580")
      (footprint "eagle-import:SO08")
      (libsource (lib "eagle-import") (part "1458DLM"))
    )
    (comp (ref "A22")
      (value "LM1458D")
      (footprint "eagle-import:SO08")
      (libsource (lib "eagle-import") (part "1458DLM"))
    )
    (comp (ref "A29")
      (value "74AHC1G14DBV")
      (footprint "eagle-import:SOT23-5")
      (libsource (lib "eagle-import") (part "741G14DBVAHC"))
    )
    (comp (ref "C19")
      (value "100n")
      (footprint "eagle-import:R0805")
      (libsource (lib "eagle-import") (part "C0805"))
    )
    (comp (ref "C20")
      (value "100n")
      (footprint "eagle-import:R0805")
      (libsource (lib "eagle-import") (part "C0805"))
    )
    (comp (ref "C21")
      (value "2n7")
      (footprint "eagle-import:R0805")
      (libsource (lib "eagle-import") (part "C0805"))
    )
    (comp (ref "C22")
      (value "2n7")
      (footprint "eagle-import:R0805")
      (libsource (lib "eagle-import") (part "C0805"))
    )
    (comp (ref "C23")
      (value "2n7")
      (footprint "eagle-import:R0805")
      (libsource (lib "eagle-import") (part "C0805"))
    )
    (comp (ref "C24")
      (value "2n7")
      (footprint "eagle-import:R0805")
      (libsource (lib "eagle-import") (part "C0805"))
    )
    (comp (ref "C25")
      (value "2n7")
      (footprint "eagle-import:R0805")
      (libsource (lib "eagle-import") (part "C0805"))
    )
    (comp (ref "C26")
      (value "2n7")
      (footprint "eagle-import:R0805")
      (libsource (lib "eagle-import") (part "C0805"))
    )
    (comp (ref "C27")
      (value "2n7")
      (footprint "eagle-import:R0805")
      (libsource (lib "eagle-import") (part "C0805"))
    )
    (comp (ref "C28")
      (value "100n")
      (footprint "eagle-import:R0805")
      (libsource (lib "eagle-import") (part "C0805"))
    )
    (comp (ref "C29")
      (value "100n")
      (footprint "eagle-import:R0805")
      (libsource (lib "eagle-import") (part "C0805"))
    )
    (comp (ref "C30")
      (value "100n")
      (footprint "eagle-import:R0805")
      (libsource (lib "eagle-import") (part "C0805"))
    )
    (comp (ref "C31")
      (value "100n")
      (footprint "eagle-import:R0805")
      (libsource (lib "eagle-import") (part "C0805"))
    )
    (comp (ref "C32")
      (value "100n")
      (footprint "eagle-import:R0805")
      (libsource (lib "eagle-import") (part "C0805"))
    )
    (comp (ref "C33")
      (value "100n")
      (footprint "eagle-import:R0805")
      (libsource (lib "eagle-import") (part "C0805"))
    )
    (comp (ref "C34")
      (value "100n")
      (footprint "eagle-import:R0805")
      (libsource (lib "eagle-import") (part "C0805"))
    )
    (comp (ref "C35")
      (value "2n7")
      (footprint "eagle-import:R0805")
      (libsource (lib "eagle-import") (part "C0805"))
    )
    (comp (ref "C36")
      (value "10u")
      (footprint "eagle-import:R0805")
      (libsource (lib "eagle-import") (part "C0805"))
    )
    (comp (ref "C37")
      (value "47p")
      (footprint "eagle-import:R0805")
      (libsource (lib "eagle-import") (part "C0805"))
    )
    (comp (ref "C38")
      (value "10u")
      (footprint "eagle-import:R0805")
      (libsource (lib "eagle-import") (part "C0805"))
    )
    (comp (ref "C39")
      (value "2n7")
      (footprint "eagle-import:R0805")
      (libsource (lib "eagle-import") (part "C0805"))
    )
    (comp (ref "C40")
      (value "CPOL-EUE3.5-8")
      (footprint "eagle-import:E3,5-8")
      (libsource (lib "eagle-import") (part "CPOL-EUE3.5-8"))
    )
    (comp (ref "C41")
      (value "2n7")
      (footprint "eagle-import:R0805")
      (libsource (lib "eagle-import") (part "C0805"))
    )
    (comp (ref "C42")
      (value "47p")
      (footprint "eagle-import:R0805")
      (libsource (lib "eagle-import") (part "C0805"))
    )
    (comp (ref "C43")
      (value "47p")
      (footprint "eagle-import:R0805")
      (libsource (lib "eagle-import") (part "C0805"))
    )
    (comp (ref "C44")
      (value "2n7")
      (footprint "eagle-import:R0805")
      (libsource (lib "eagle-import") (part "C0805"))
    )
    (comp (ref "C45")
      (value "10u")
      (footprint "eagle-import:R0805")
      (libsource (lib "eagle-import") (part "C0805"))
    )
    (comp (ref "C46")
      (value "10u")
      (footprint "eagle-import:R0805")
      (libsource (lib "eagle-import") (part "C0805"))
    )
    (comp (ref "C47")
      (value "CPOL-EUE3.5-8")
      (footprint "eagle-import:E3,5-8")
      (libsource (lib "eagle-import") (part "CPOL-EUE3.5-8"))
    )
    (comp (ref "C48")
      (value "2n7")
      (footprint "eagle-import:R0805")
      (libsource (lib "eagle-import") (part "C0805"))
    )
    (comp (ref "C49")
      (value "47p")
      (footprint "eagle-import:R0805")
      (libsource (lib "eagle-import") (part "C0805"))
    )
    (comp (ref "C50")
      (value "10u")
      (footprint "eagle-import:R0805")
      (libsource (lib "eagle-import") (part "C0805"))
    )
    (comp (ref "C51")
      (value "10u")
      (footprint "eagle-import:R0805")
      (libsource (lib "eagle-import") (part "C0805"))
    )
    (comp (ref "C61")
      (value "100n")
      (footprint "eagle-import:R0805")
      (libsource (lib "eagle-import") (part "C0805"))
    )
    (comp (ref "C62")
      (value "100n")
      (footprint "eagle-import:R0805")
      (libsource (lib "eagle-import") (part "C0805"))
    )
    (comp (ref "C63")
      (value "100n")
      (footprint "eagle-import:R0805")
      (libsource (lib "eagle-import") (part "C0805"))
    )
    (comp (ref "C64")
      (value "100n")
      (footprint "eagle-import:R0805")
      (libsource (lib "eagle-import") (part "C0805"))
    )
    (comp (ref "C68")
      (value "100n")
      (footprint "eagle-import:R0805")
      (libsource (lib "eagle-import") (part "C0805"))
    )
    (comp (ref "C70")
      (value "100n")
      (footprint "eagle-import:R0805")
      (libsource (lib "eagle-import") (part "C0805"))
    )
    (comp (ref "C72")
      (value "100n")
      (footprint "eagle-import:R0805")
      (libsource (lib "eagle-import") (part "C0805"))
    )
    (comp (ref "C73")
      (value "100n")
      (footprint "eagle-import:R0805")
      (libsource (lib "eagle-import") (part "C0805"))
    )
    (comp (ref "C76")
      (value "100n")
      (footprint "eagle-import:R0805")
      (libsource (lib "eagle-import") (part "C0805"))
    )
    (comp (ref "C79")
      (value "100n")
      (footprint "eagle-import:R0805")
      (libsource (lib "eagle-import") (part "C0805"))
    )
    (comp (ref "D5")
      (value "LL4148")
      (footprint "eagle-import:SOD80C")
      (libsource (lib "eagle-import") (part "DIODE-SOD80C"))
    )
    (comp (ref "M1")
      (value "MIDIJACK")
      (footprint "eagle-import:CP-2350")
      (libsource (lib "eagle-import") (part "MIDIJACK"))
    )
    (comp (ref "M2")
      (value "MIDIJACK")
      (footprint "eagle-import:CP-2350")
      (libsource (lib "eagle-import") (part "MIDIJACK"))
    )
    (comp (ref "OK1")
      (value "PC817")
      (footprint "eagle-import:DIL04")
      (fields (field (name "MPN") "PC817X4J000F"))
      (libsource (lib "eagle-import") (part "PC817"))
    )
    (comp (ref "R17")
      (value "33")
      (footprint "eagle-import:R0805")
      (libsource (lib "eagle-import") (part "R0805"))
    )
    (comp (ref "R18")
      (value "10k")
      (footprint "eagle-import:CA6V")
      (libsource (lib "eagle-import") (part "TRIM_EU-CA6V"))
    )
    (comp (ref "R19")
      (value "10k")
      (footprint "eagle-import:R0805")
      (libsource (lib "eagle-import") (part "R0805"))
    )
    (comp (ref "R20")
      (value "4k7")
      (footprint "eagle-import:R0805")
      (libsource (lib "eagle-import") (part "R0805"))
    )
    (comp (ref "R21")
      (value "100")
      (footprint "eagle-import:R0805")
      (libsource (lib "eagle-import") (part "R0805"))
    )
    (comp (ref "R22")
      (value "4k7")
      (footprint "eagle-import:R0805")
      (libsource (lib "eagle-import") (part "R0805"))
    )
    (comp (ref "R23")
      (value "100")
      (footprint "eagle-import:R0805")
      (libsource (lib "eagle-import") (part "R0805"))
    )
    (comp (ref "R24")
      (value "10k")
      (footprint "eagle-import:R0805")
      (libsource (lib "eagle-import") (part "R0805"))
    )
    (comp (ref "R25")
      (value "10k")
      (footprint "eagle-import:CA6V")
      (libsource (lib "eagle-import") (part "TRIM_EU-CA6V"))
    )
    (comp (ref "R26")
      (value "4k7")
      (footprint "eagle-import:R0805")
      (libsource (lib "eagle-import") (part "R0805"))
    )
    (comp (ref "R27")
      (value "4k7")
      (footprint "eagle-import:R0805")
      (libsource (lib "eagle-import") (part "R0805"))
    )
    (comp (ref "R28")
      (value "100")
      (footprint "eagle-import:R0805")
      (libsource (lib "eagle-import") (part "R0805"))
    )
    (comp (ref "R29")
      (value "100")
      (footprint "eagle-import:R0805")
      (libsource (lib "eagle-import") (part "R0805"))
    )
    (comp (ref "R34")
      (value "33")
      (footprint "eagle-import:R0805")
      (libsource (lib "eagle-import") (part "R0805"))
    )
    (comp (ref "R35")
      (value "10k")
      (footprint "eagle-import:R0805")
      (libsource (lib "eagle-import") (part "R0805"))
    )
    (comp (ref "R36")
      (value "10k")
      (footprint "eagle-import:R0805")
      (libsource (lib "eagle-import") (part "R0805"))
    )
    (comp (ref "R37")
      (value "33")
      (footprint "eagle-import:R0805")
      (libsource (lib "eagle-import") (part "R0805"))
    )
    (comp (ref "R42")
      (value "10k")
      (footprint "eagle-import:R0805")
      (libsource (lib "eagle-import") (part "R0805"))
    )
    (comp (ref "R44")
      (value "10k")
      (footprint "eagle-import:R0805")
      (libsource (lib "eagle-import") (part "R0805"))
    )
    (comp (ref "R58")
      (value "33")
      (footprint "eagle-import:R0805")
      (libsource (lib "eagle-import") (part "R0805"))
    )
    (comp (ref "R61")
      (value "100")
      (footprint "eagle-import:R0805")
      (libsource (lib "eagle-import") (part "R0805"))
    )
    (comp (ref "R62")
      (value "10k")
      (footprint "eagle-import:R0805")
      (libsource (lib "eagle-import") (part "R0805"))
    )
    (comp (ref "R65")
      (value "10k")
      (footprint "eagle-import:R0805")
      (libsource (lib "eagle-import") (part "R0805"))
    )
    (comp (ref "R66")
      (value "10k")
      (footprint "eagle-import:R0805")
      (libsource (lib "eagle-import") (part "R0805"))
    )
    (comp (ref "R77")
      (value "100")
      (footprint "eagle-import:R0805")
      (libsource (lib "eagle-import") (part "R0805"))
    )
    (comp (ref "R78")
      (value "100")
      (footprint "eagle-import:R0805")
      (libsource (lib "eagle-import") (part "R0805"))
    )
    (comp (ref "X1")
      (value "STEREOJACK")
      (footprint "eagle-import:STX3100")
      (libsource (lib "eagle-import") (part "STEREOJACK"))
    )
  )
  (nets
    (net (code "1") (name "+3V3") (class "Default")
      (node (ref "A1") (pin "36") (pinfunction "3V3(OUT)_36") (pintype "bidirectional"))
      (node (ref "A2") (pin "14") (pinfunction "VCC_14") (pintype "power_in"))
      (node (ref "A23") (pin "16") (pinfunction "VCC_16") (pintype "power_in"))
      (node (ref "A24") (pin "16") (pinfunction "VCC_16") (pintype "power_in"))
      (node (ref "A28") (pin "5") (pinfunction "+IN_5") (pintype "input"))
      (node (ref "A28") (pin "8") (pinfunction "V+_8") (pintype "power_in"))
      (node (ref "C17") (pin "2") (pinfunction "2_2") (pintype "passive"))
      (node (ref "C18") (pin "2") (pinfunction "2_2") (pintype "passive"))
      (node (ref "C76") (pin "2") (pinfunction "2_2") (pintype "passive"))
      (node (ref "C77") (pin "2") (pinfunction "2_2") (pintype "passive"))
      (node (ref "C80") (pin "2") (pinfunction "2_2") (pintype "passive"))
      (node (ref "D7") (pin "A") (pinfunction "A_A") (pintype "passive"))
      (node (ref "J1") (pin "2") (pinfunction "2_2") (pintype "passive"))
      (node (ref "JP1") (pin "5") (pinfunction "5_5") (pintype "passive"))
      (node (ref "K4") (pin "1") (pinfunction "1_1") (pintype "bidirectional"))
      (node (ref "P1") (pin "E") (pinfunction "E_E") (pintype "passive"))
      (node (ref "P10") (pin "E") (pinfunction "E_E") (pintype "passive"))
      (node (ref "P2") (pin "E") (pinfunction "E_E") (pintype "passive"))
      (node (ref "P3") (pin "E") (pinfunction "E_E") (pintype "passive"))
      (node (ref "P4") (pin "E") (pinfunction "E_E") (pintype "passive"))
      (node (ref "P6") (pin "E") (pinfunction "E_E") (pintype "passive"))
      (node (ref "P8") (pin "E") (pinfunction "E_E") (pintype "passive"))
      (node (ref "Q1") (pin "C") (pinfunction "C_C") (pintype "bidirectional"))
      (node (ref "Q10") (pin "C") (pinfunction "C_C") (pintype "bidirectional"))
      (node (ref "Q11") (pin "C") (pinfunction "C_C") (pintype "bidirectional"))
      (node (ref "Q12") (pin "C") (pinfunction "C_C") (pintype "bidirectional"))
      (node (ref "Q2") (pin "C") (pinfunction "C_C") (pintype "bidirectional"))
      (node (ref "Q3") (pin "C") (pinfunction "C_C") (pintype "bidirectional"))
      (node (ref "Q4") (pin "C") (pinfunction "C_C") (pintype "bidirectional"))
      (node (ref "Q5") (pin "C") (pinfunction "C_C") (pintype "bidirectional"))
      (node (ref "Q6") (pin "C") (pinfunction "C_C") (pintype "bidirectional"))
      (node (ref "Q7") (pin "C") (pinfunction "C_C") (pintype "bidirectional"))
      (node (ref "Q8") (pin "C") (pinfunction "C_C") (pintype "bidirectional"))
      (node (ref "Q9") (pin "C") (pinfunction "C_C") (pintype "bidirectional"))
      (node (ref "R1") (pin "1") (pinfunction "2_1") (pintype "passive"))
      (node (ref "R10") (pin "1") (pinfunction "2_1") (pintype "passive"))
      (node (ref "R11") (pin "1") (pinfunction "2_1") (pintype "passive"))
      (node (ref "R12") (pin "1") (pinfunction "2_1") (pintype "passive"))
      (node (ref "R13") (pin "1") (pinfunction "2_1") (pintype "passive"))
      (node (ref "R14") (pin "1") (pinfunction "2_1") (pintype "passive"))
      (node (ref "R15") (pin "1") (pinfunction "2_1") (pintype "passive"))
      (node (ref "R16") (pin "1") (pinfunction "2_1") (pintype "passive"))
      (node (ref "R2") (pin "1") (pinfunction "2_1") (pintype "passive"))
      (node (ref "R3") (pin "1") (pinfunction "2_1") (pintype "passive"))
      (node (ref "R4") (pin "1") (pinfunction "2_1") (pintype "passive"))
      (node (ref "R45") (pin "1") (pinfunction "2_1") (pintype "passive"))
      (node (ref "R5") (pin "1") (pinfunction "2_1") (pintype "passive"))
      (node (ref "R54") (pin "1") (pinfunction "2_1") (pintype "passive"))
      (node (ref "R56") (pin "E") (pinfunction "E_E") (pintype "passive"))
      (node (ref "R57") (pin "E") (pinfunction "E_E") (pintype "passive"))
      (node (ref "R6") (pin "1") (pinfunction "2_1") (pintype "passive"))
      (node (ref "R65") (pin "1") (pinfunction "2_1") (pintype "passive"))
      (node (ref "R7") (pin "1") (pinfunction "2_1") (pintype "passive"))
      (node (ref "R74") (pin "E") (pinfunction "E_E") (pintype "passive"))
      (node (ref "R77") (pin "2") (pinfunction "1_2") (pintype "passive"))
      (node (ref "R8") (pin "1") (pinfunction "2_1") (pintype "passive"))
      (node (ref "R9") (pin "1") (pinfunction "2_1") (pintype "passive"))
    )
    (net (code "2") (name "+5V") (class "Default")
      (node (ref "A1") (pin "39") (pinfunction "VSYS_39") (pintype "bidirectional"))
      (node (ref "A10") (pin "8") (pinfunction "V+_8") (pintype "power_in"))
      (node (ref "A11") (pin "8") (pinfunction "V+_8") (pintype "power_in"))
      (node (ref "A12") (pin "8") (pinfunction "V+_8") (pintype "power_in"))
      (node (ref "A13") (pin "8") (pinfunction "V+_8") (pintype "power_in"))
      (node (ref "A14") (pin "10") (pinfunction "SCL_10") (pintype "input"))
      (node (ref "A14") (pin "16") (pinfunction "VCC_16") (pintype "power_in"))
      (node (ref "A15") (pin "1") (pinfunction "VDD_1") (pintype "bidirectional"))
      (node (ref "A15") (pin "7") (pinfunction "~{RD}_7") (pintype "bidirectional"))
      (node (ref "A16") (pin "1") (pinfunction "VDD_1_1") (pintype "bidirectional"))
      (node (ref "A16") (pin "3") (pinfunction "VDD_2_3") (pintype "bidirectional"))
      (node (ref "A16") (pin "6") (pinfunction "FSEL_6") (pintype "bidirectional"))
      (node (ref "A16") (pin "9") (pinfunction "TST1_9") (pintype "bidirectional"))
      (node (ref "A17") (pin "1") (pinfunction "VDD_1_1") (pintype "bidirectional"))
      (node (ref "A17") (pin "3") (pinfunction "VDD_2_3") (pintype "bidirectional"))
      (node (ref "A17") (pin "6") (pinfunction "FSEL_6") (pintype "bidirectional"))
      (node (ref "A17") (pin "9") (pinfunction "TST1_9") (pintype "bidirectional"))
      (node (ref "A18") (pin "8") (pinfunction "V+_8") (pintype "power_in"))
      (node (ref "A19") (pin "8") (pinfunction "V+_8") (pintype "power_in"))
      (node (ref "A20") (pin "8") (pinfunction "V+_8") (pintype "power_in"))
      (node (ref "A21") (pin "8") (pinfunction "V+_8") (pintype "power_in"))
      (node (ref "A22") (pin "8") (pinfunction "V+_8") (pintype "power_in"))
      (node (ref "A29") (pin "5") (pinfunction "VCC_5") (pintype "power_in"))
      (node (ref "A3") (pin "2") (pinfunction "VO_2") (pintype "passive"))
      (node (ref "A4") (pin "14") (pinfunction "VCC_14") (pintype "power_in"))
      (node (ref "A5") (pin "14") (pinfunction "VCC_14") (pintype "power_in"))
      (node (ref "A6") (pin "10") (pinfunction "SCL_10") (pintype "input"))
      (node (ref "A6") (pin "16") (pinfunction "VCC_16") (pintype "power_in"))
      (node (ref "A7") (pin "1") (pinfunction "VDD_1") (pintype "bidirectional"))
      (node (ref "A7") (pin "7") (pinfunction "~{RD}_7") (pintype "bidirectional"))
      (node (ref "A8") (pin "1") (pinfunction "VDD_1_1") (pintype "bidirectional"))
      (node (ref "A8") (pin "3") (pinfunction "VDD_2_3") (pintype "bidirectional"))
      (node (ref "A8") (pin "6") (pinfunction "FSEL_6") (pintype "bidirectional"))
      (node (ref "A8") (pin "9") (pinfunction "TST1_9") (pintype "bidirectional"))
      (node (ref "A9") (pin "1") (pinfunction "VDD_1_1") (pintype "bidirectional"))
      (node (ref "A9") (pin "3") (pinfunction "VDD_2_3") (pintype "bidirectional"))
      (node (ref "A9") (pin "6") (pinfunction "FSEL_6") (pintype "bidirectional"))
      (node (ref "A9") (pin "9") (pinfunction "TST1_9") (pintype "bidirectional"))
      (node (ref "C19") (pin "2") (pinfunction "2_2") (pintype "passive"))
      (node (ref "C20") (pin "2") (pinfunction "2_2") (pintype "passive"))
      (node (ref "C28") (pin "1") (pinfunction "1_1") (pintype "passive"))
      (node (ref "C29") (pin "2") (pinfunction "2_2") (pintype "passive"))
      (node (ref "C30") (pin "2") (pinfunction "2_2") (pintype "passive"))
      (node (ref "C31") (pin "2") (pinfunction "2_2") (pintype "passive"))
      (node (ref "C32") (pin "2") (pinfunction "2_2") (pintype "passive"))
      (node (ref "C33") (pin "2") (pinfunction "2_2") (pintype "passive"))
      (node (ref "C34") (pin "2") (pinfunction "2_2") (pintype "passive"))
      (node (ref "C52") (pin "2") (pinfunction "2_2") (pintype "passive"))
      (node (ref "C60") (pin "2") (pinfunction "2_2") (pintype "passive"))
      (node (ref "C61") (pin "2") (pinfunction "2_2") (pintype "passive"))
      (node (ref "C62") (pin "2") (pinfunction "2_2") (pintype "passive"))
      (node (ref "C63") (pin "2") (pinfunction "2_2") (pintype "passive"))
      (node (ref "C64") (pin "2") (pinfunction "2_2") (pintype "passive"))
      (node (ref "C68") (pin "2") (pinfunction "2_2") (pintype "passive"))
      (node (ref "C70") (pin "2") (pinfunction "2_2") (pintype "passive"))
      (node (ref "C72") (pin "2") (pinfunction "2_2") (pintype "passive"))
      (node (ref "C73") (pin "2") (pinfunction "2_2") (pintype "passive"))
      (node (ref "C78") (pin "2") (pinfunction "2_2") (pintype "passive"))
      (node (ref "C79") (pin "2") (pinfunction "2_2") (pintype "passive"))
      (node (ref "C81") (pin "2") (pinfunction "2_2") (pintype "passive"))
      (node (ref "C82") (pin "2") (pinfunction "2_2") (pintype "passive"))
      (node (ref "D1") (pin "A") (pinfunction "A_A") (pintype "passive"))
      (node (ref "D6") (pin "A") (pinfunction "A_A") (pintype "passive"))
      (node (ref "JP1") (pin "6") (pinfunction "6_6") (pintype "passive"))
      (node (ref "K1") (pin "1") (pinfunction "1_1") (pintype "bidirectional"))
      (node (ref "R30") (pin "1") (pinfunction "2_1") (pintype "passive"))
      (node (ref "R31") (pin "1") (pinfunction "2_1") (pintype "passive"))
      (node (ref "R32") (pin "1") (pinfunction "2_1") (pintype "passive"))
      (node (ref "R33") (pin "1") (pinfunction "2_1") (pintype "passive"))
    )
    (net (code "3") (name "+9V") (class "Default")
      (node (ref "A25") (pin "16") (pinfunction "VCC_16") (pintype "power_in"))
      (node (ref "A26") (pin "16") (pinfunction "VCC_16") (pintype "power_in"))
      (node (ref "A27") (pin "16") (pinfunction "VCC_16") (pintype "power_in"))
      (node (ref "C56") (pin "2") (pinfunction "2_2") (pintype "passive"))
      (node (ref "C57") (pin "2") (pinfunction "2_2") (pintype "passive"))
      (node (ref "C58") (pin "2") (pinfunction "2_2") (pintype "passive"))
      (node (ref "C71") (pin "2") (pinfunction "2_2") (pintype "passive"))
      (node (ref "D2") (pin "C") (pinfunction "C_C") (pintype "passive"))
      (node (ref "D8") (pin "A") (pinfunction "A_A") (pintype "passive"))
      (node (ref "K2") (pin "1") (pinfunction "1_1") (pintype "bidirectional"))
    )
    (net (code "4") (name "-5V") (class "Default")
      (node (ref "A25") (pin "7") (pinfunction "VEE_7") (pintype "power_in"))
      (node (ref "A26") (pin "7") (pinfunction "VEE_7") (pintype "power_in"))
      (node (ref "A27") (pin "7") (pinfunction "VEE_7") (pintype "power_in"))
      (node (ref "C53") (pin "1") (pinfunction "1_1") (pintype "passive"))
      (node (ref "C54") (pin "1") (pinfunction "1_1") (pintype "passive"))
      (node (ref "C55") (pin "1") (pinfunction "1_1") (pintype "passive"))
      (node (ref "C69") (pin "2") (pinfunction "2_2") (pintype "passive"))
      (node (ref "D4") (pin "A") (pinfunction "A_A") (pintype "passive"))
      (node (ref "D9") (pin "K") (pinfunction "C_K") (pintype "passive"))
      (node (ref "K3") (pin "1") (pinfunction "1_1") (pintype "bidirectional"))
    )
    (net (code "5") (name "14.32MHZ") (class "Default")
      (node (ref "A15") (pin "24") (pinfunction "ØM_24") (pintype "bidirectional"))
      (node (ref "A4") (pin "8") (pinfunction "O_8") (pintype "output"))
      (node (ref "A7") (pin "24") (pinfunction "ØM_24") (pintype "bidirectional"))
    )
    (net (code "6") (name "A0") (class "Default")
      (node (ref "A1") (pin "19") (pinfunction "GP14_19") (pintype "bidirectional"))
      (node (ref "A15") (pin "4") (pinfunction "A0_4") (pintype "bidirectional"))
      (node (ref "A7") (pin "4") (pinfunction "A0_4") (pintype "bidirectional"))
    )
    (net (code "7") (name "A1") (class "Default")
      (node (ref "A1") (pin "20") (pinfunction "GP15_20") (pintype "bidirectional"))
      (node (ref "A15") (pin "5") (pinfunction "A1_5") (pintype "bidirectional"))
      (node (ref "A7") (pin "5") (pinfunction "A1_5") (pintype "bidirectional"))
    )
    (net (code "8") (name "A2") (class "Default")
      (node (ref "A1") (pin "11") (pinfunction "GP8_11") (pintype "bidirectional"))
      (node (ref "A25") (pin "11") (pinfunction "A_11") (pintype "input"))
      (node (ref "A26") (pin "11") (pinfunction "A_11") (pintype "input"))
      (node (ref "JP1") (pin "3") (pinfunction "3_3") (pintype "passive"))
      (node (ref "K5") (pin "1") (pinfunction "1_1") (pintype "bidirectional"))
    )
    (net (code "9") (name "A3") (class "Default")
      (node (ref "A1") (pin "15") (pinfunction "GP11_15") (pintype "bidirectional"))
      (node (ref "A27") (pin "11") (pinfunction "A_11") (pintype "input"))
      (node (ref "K8") (pin "1") (pinfunction "1_1") (pintype "bidirectional"))
    )
    (net (code "10") (name "ADC") (class "Default")
      (node (ref "A1") (pin "31") (pinfunction "GP26_A0_31") (pintype "bidirectional"))
      (node (ref "A27") (pin "3") (pinfunction "X_3") (pintype "bidirectional"))
      (node (ref "A28") (pin "3") (pinfunction "+IN_3") (pintype "input"))
    )
    (net (code "11") (name "ANALOG_COMP") (class "Default")
      (node (ref "A1") (pin "32") (pinfunction "GP27_A1_32") (pintype "bidirectional"))
      (node (ref "A28") (pin "1") (pinfunction "OUT_1") (pintype "output"))
      (node (ref "R54") (pin "2") (pinfunction "1_2") (pintype "passive"))
    )
    (net (code "12") (name "B2") (class "Default")
      (node (ref "A1") (pin "12") (pinfunction "GP9_12") (pintype "bidirectional"))
      (node (ref "A25") (pin "10") (pinfunction "B_10") (pintype "input"))
      (node (ref "A26") (pin "10") (pinfunction "B_10") (pintype "input"))
      (node (ref "K7") (pin "1") (pinfunction "1_1") (pintype "bidirectional"))
    )
    (net (code "13") (name "B3") (class "Default")
      (node (ref "A1") (pin "16") (pinfunction "GP12_16") (pintype "bidirectional"))
      (node (ref "A27") (pin "10") (pinfunction "B_10") (pintype "input"))
      (node (ref "K9") (pin "1") (pinfunction "1_1") (pintype "bidirectional"))
    )
    (net (code "14") (name "C2") (class "Default")
      (node (ref "A1") (pin "14") (pinfunction "GP10_14") (pintype "bidirectional"))
      (node (ref "A25") (pin "9") (pinfunction "C_9") (pintype "input"))
      (node (ref "A26") (pin "9") (pinfunction "C_9") (pintype "input"))
      (node (ref "K6") (pin "1") (pinfunction "1_1") (pintype "bidirectional"))
    )
    (net (code "15") (name "C3") (class "Default")
      (node (ref "A1") (pin "17") (pinfunction "GP13_17") (pintype "bidirectional"))
      (node (ref "A27") (pin "9") (pinfunction "C_9") (pintype "input"))
      (node (ref "K10") (pin "1") (pinfunction "1_1") (pintype "bidirectional"))
    )
    (net (code "16") (name "CLEAR") (class "Default")
      (node (ref "A1") (pin "21") (pinfunction "GP16_21") (pintype "bidirectional"))
      (node (ref "A15") (pin "3") (pinfunction "~{IC}_3") (pintype "bidirectional"))
      (node (ref "A7") (pin "3") (pinfunction "~{IC}_3") (pintype "bidirectional"))
    )
    (net (code "17") (name "DATA") (class "Default")
      (node (ref "A1") (pin "25") (pinfunction "GP19_25") (pintype "bidirectional"))
      (node (ref "A14") (pin "14") (pinfunction "SER_14") (pintype "input"))
    )
    (net (code "18") (name "GND") (class "Default")
      (node (ref "A1") (pin "13") (pinfunction "GND_3_13") (pintype "bidirectional"))
      (node (ref "A1") (pin "18") (pinfunction "GND_4_18") (pintype "bidirectional"))
      (node (ref "A1") (pin "23") (pinfunction "GND_5_23") (pintype "bidirectional"))
      (node (ref "A1") (pin "28") (pinfunction "GND_6_28") (pintype "bidirectional"))
      (node (ref "A1") (pin "3") (pinfunction "GND_1_3") (pintype "bidirectional"))
      (node (ref "A1") (pin "33") (pinfunction "GND_7_33") (pintype "bidirectional"))
      (node (ref "A1") (pin "38") (pinfunction "GND_8_38") (pintype "bidirectional"))
      (node (ref "A1") (pin "8") (pinfunction "GND_2_8") (pintype "bidirectional"))
      (node (ref "A1") (pin "D2") (pinfunction "GND_9_D2") (pintype "bidirectional"))
      (node (ref "A1") (pin "TP1") (pinfunction "GND_10_TP1") (pintype "bidirectional"))
      (node (ref "A10") (pin "4") (pinfunction "V-_4") (pintype "power_in"))
      (node (ref "A11") (pin "4") (pinfunction "V-_4") (pintype "power_in"))
      (node (ref "A12") (pin "4") (pinfunction "V-_4") (pintype "power_in"))
      (node (ref "A13") (pin "4") (pinfunction "V-_4") (pintype "power_in"))
      (node (ref "A14") (pin "13") (pinfunction "G_13") (pintype "input"))
      (node (ref "A14") (pin "8") (pinfunction "GND_8") (pintype "power_in"))
      (node (ref "A15") (pin "12") (pinfunction "VSS_12") (pintype "bidirectional"))
      (node (ref "A16") (pin "2") (pinfunction "VSS_2") (pintype "bidirectional"))
      (node (ref "A17") (pin "2") (pinfunction "VSS_2") (pintype "bidirectional"))
      (node (ref "A18") (pin "4") (pinfunction "V-_4") (pintype "power_in"))
      (node (ref "A19") (pin "4") (pinfunction "V-_4") (pintype "power_in"))
      (node (ref "A2") (pin "7") (pinfunction "GND_7") (pintype "power_in"))
      (node (ref "A20") (pin "4") (pinfunction "V-_4") (pintype "power_in"))
      (node (ref "A21") (pin "4") (pinfunction "V-_4") (pintype "power_in"))
      (node (ref "A22") (pin "4") (pinfunction "V-_4") (pintype "power_in"))
      (node (ref "A23") (pin "10") (pinfunction "SER_10") (pintype "input"))
      (node (ref "A23") (pin "8") (pinfunction "GND_8") (pintype "power_in"))
      (node (ref "A24") (pin "8") (pinfunction "GND_8") (pintype "power_in"))
      (node (ref "A25") (pin "6") (pinfunction "INH_6") (pintype "input"))
      (node (ref "A25") (pin "8") (pinfunction "GND_8") (pintype "power_in"))
      (node (ref "A26") (pin "6") (pinfunction "INH_6") (pintype "input"))
      (node (ref "A26") (pin "8") (pinfunction "GND_8") (pintype "power_in"))
      (node (ref "A27") (pin "6") (pinfunction "INH_6") (pintype "input"))
      (node (ref "A27") (pin "8") (pinfunction "GND_8") (pintype "power_in"))
      (node (ref "A28") (pin "4") (pinfunction "V-_4") (pintype "power_in"))
      (node (ref "A28") (pin "6") (pinfunction "-IN_6") (pintype "input"))
      (node (ref "A29") (pin "3") (pinfunction "GND_3") (pintype "power_in"))
      (node (ref "A3") (pin "3") (pinfunction "GND_3") (pintype "passive"))
      (node (ref "A4") (pin "7") (pinfunction "GND_7") (pintype "power_in"))
      (node (ref "A5") (pin "7") (pinfunction "GND_7") (pintype "power_in"))
      (node (ref "A6") (pin "13") (pinfunction "G_13") (pintype "input"))
      (node (ref "A6") (pin "8") (pinfunction "GND_8") (pintype "power_in"))
      (node (ref "A7") (pin "12") (pinfunction "VSS_12") (pintype "bidirectional"))
      (node (ref "A8") (pin "2") (pinfunction "VSS_2") (pintype "bidirectional"))
      (node (ref "A9") (pin "2") (pinfunction "VSS_2") (pintype "bidirectional"))
      (node (ref "C1") (pin "1") (pinfunction "1_1") (pintype "passive"))
      (node (ref "C10") (pin "1") (pinfunction "1_1") (pintype "passive"))
      (node (ref "C11") (pin "1") (pinfunction "1_1") (pintype "passive"))
      (node (ref "C12") (pin "1") (pinfunction "1_1") (pintype "passive"))
      (node (ref "C13") (pin "1") (pinfunction "1_1") (pintype "passive"))
      (node (ref "C14") (pin "1") (pinfunction "1_1") (pintype "passive"))
      (node (ref "C15") (pin "1") (pinfunction "1_1") (pintype "passive"))
      (node (ref "C16") (pin "1") (pinfunction "1_1") (pintype "passive"))
      (node (ref "C17") (pin "1") (pinfunction "1_1") (pintype "passive"))
      (node (ref "C18") (pin "1") (pinfunction "1_1") (pintype "passive"))
      (node (ref "C19") (pin "1") (pinfunction "1_1") (pintype "passive"))
      (node (ref "C2") (pin "1") (pinfunction "1_1") (pintype "passive"))
      (node (ref "C20") (pin "1") (pinfunction "1_1") (pintype "passive"))
      (node (ref "C21") (pin "1") (pinfunction "1_1") (pintype "passive"))
      (node (ref "C22") (pin "1") (pinfunction "1_1") (pintype "passive"))
      (node (ref "C23") (pin "1") (pinfunction "1_1") (pintype "passive"))
      (node (ref "C24") (pin "1") (pinfunction "1_1") (pintype "passive"))
      (node (ref "C25") (pin "1") (pinfunction "1_1") (pintype "passive"))
      (node (ref "C26") (pin "1") (pinfunction "1_1") (pintype "passive"))
      (node (ref "C27") (pin "1") (pinfunction "1_1") (pintype "passive"))
      (node (ref "C28") (pin "2") (pinfunction "2_2") (pintype "passive"))
      (node (ref "C29") (pin "1") (pinfunction "1_1") (pintype "passive"))
      (node (ref "C3") (pin "1") (pinfunction "1_1") (pintype "passive"))
      (node (ref "C30") (pin "1") (pinfunction "1_1") (pintype "passive"))
      (node (ref "C31") (pin "1") (pinfunction "1_1") (pintype "passive"))
      (node (ref "C32") (pin "1") (pinfunction "1_1") (pintype "passive"))
      (node (ref "C33") (pin "1") (pinfunction "1_1") (pintype "passive"))
      (node (ref "C34") (pin "1") (pinfunction "1_1") (pintype "passive"))
      (node (ref "C35") (pin "1") (pinfunction "1_1") (pintype "passive"))
      (node (ref "C36") (pin "1") (pinfunction "1_1") (pintype "passive"))
      (node (ref "C37") (pin "1") (pinfunction "1_1") (pintype "passive"))
      (node (ref "C38") (pin "1") (pinfunction "1_1") (pintype "passive"))
      (node (ref "C39") (pin "1") (pinfunction "1_1") (pintype "passive"))
      (node (ref "C4") (pin "1") (pinfunction "1_1") (pintype "passive"))
      (node (ref "C41") (pin "1") (pinfunction "1_1") (pintype "passive"))
      (node (ref "C42") (pin "1") (pinfunction "1_1") (pintype "passive"))
      (node (ref "C43") (pin "1") (pinfunction "1_1") (pintype "passive"))
      (node (ref "C45") (pin "1") (pinfunction "1_1") (pintype "passive"))
      (node (ref "C46") (pin "1") (pinfunction "1_1") (pintype "passive"))
      (node (ref "C49") (pin "1") (pinfunction "1_1") (pintype "passive"))
      (node (ref "C5") (pin "1") (pinfunction "1_1") (pintype "passive"))
      (node (ref "C50") (pin "1") (pinfunction "1_1") (pintype "passive"))
      (node (ref "C51") (pin "1") (pinfunction "1_1") (pintype "passive"))
      (node (ref "C52") (pin "1") (pinfunction "1_1") (pintype "passive"))
      (node (ref "C53") (pin "2") (pinfunction "2_2") (pintype "passive"))
      (node (ref "C54") (pin "2") (pinfunction "2_2") (pintype "passive"))
      (node (ref "C55") (pin "2") (pinfunction "2_2") (pintype "passive"))
      (node (ref "C56") (pin "1") (pinfunction "1_1") (pintype "passive"))
      (node (ref "C57") (pin "1") (pinfunction "1_1") (pintype "passive"))
      (node (ref "C58") (pin "1") (pinfunction "1_1") (pintype "passive"))
      (node (ref "C59") (pin "1") (pinfunction "1_1") (pintype "passive"))
      (node (ref "C6") (pin "1") (pinfunction "1_1") (pintype "passive"))
      (node (ref "C60") (pin "1") (pinfunction "1_1") (pintype "passive"))
      (node (ref "C61") (pin "1") (pinfunction "1_1") (pintype "passive"))
      (node (ref "C62") (pin "1") (pinfunction "1_1") (pintype "passive"))
      (node (ref "C63") (pin "1") (pinfunction "1_1") (pintype "passive"))
      (node (ref "C64") (pin "1") (pinfunction "1_1") (pintype "passive"))
      (node (ref "C65") (pin "1") (pinfunction "1_1") (pintype "passive"))
      (node (ref "C68") (pin "1") (pinfunction "1_1") (pintype "passive"))
      (node (ref "C69") (pin "1") (pinfunction "1_1") (pintype "passive"))
      (node (ref "C7") (pin "1") (pinfunction "1_1") (pintype "passive"))
      (node (ref "C70") (pin "1") (pinfunction "1_1") (pintype "passive"))
      (node (ref "C71") (pin "1") (pinfunction "1_1") (pintype "passive"))
      (node (ref "C72") (pin "1") (pinfunction "1_1") (pintype "passive"))
      (node (ref "C73") (pin "1") (pinfunction "1_1") (pintype "passive"))
      (node (ref "C74") (pin "1") (pinfunction "1_1") (pintype "passive"))
      (node (ref "C75") (pin "1") (pinfunction "1_1") (pintype "passive"))
      (node (ref "C76") (pin "1") (pinfunction "1_1") (pintype "passive"))
      (node (ref "C77") (pin "1") (pinfunction "1_1") (pintype "passive"))
      (node (ref "C78") (pin "1") (pinfunction "1_1") (pintype "passive"))
      (node (ref "C79") (pin "1") (pinfunction "1_1") (pintype "passive"))
      (node (ref "C8") (pin "1") (pinfunction "1_1") (pintype "passive"))
      (node (ref "C80") (pin "1") (pinfunction "1_1") (pintype "passive"))
      (node (ref "C81") (pin "1") (pinfunction "1_1") (pintype "passive"))
      (node (ref "C82") (pin "1") (pinfunction "1_1") (pintype "passive"))
      (node (ref "C9") (pin "1") (pinfunction "1_1") (pintype "passive"))
      (node (ref "D3") (pin "C") (pinfunction "C_C") (pintype "passive"))
      (node (ref "J2") (pin "3") (pinfunction "3_3") (pintype "passive"))
      (node (ref "JP1") (pin "4") (pinfunction "4_4") (pintype "passive"))
      (node (ref "JP2") (pin "1") (pinfunction "1_1") (pintype "passive"))
      (node (ref "JP3") (pin "1") (pinfunction "1_1") (pintype "passive"))
      (node (ref "JP4") (pin "1") (pinfunction "1_1") (pintype "passive"))
      (node (ref "L12") (pin "K") (pinfunction "C_K") (pintype "passive"))
      (node (ref "L3") (pin "K") (pinfunction "C_K") (pintype "passive"))
      (node (ref "L6") (pin "K") (pinfunction "C_K") (pintype "passive"))
      (node (ref "L9") (pin "K") (pinfunction "C_K") (pintype "passive"))
      (node (ref "M2") (pin "2") (pinfunction "2_2") (pintype "passive"))
      (node (ref "OK1") (pin "3") (pinfunction "EMIT_3") (pintype "passive"))
      (node (ref "P1") (pin "A") (pinfunction "A_A") (pintype "passive"))
      (node (ref "P10") (pin "A") (pinfunction "A_A") (pintype "passive"))
      (node (ref "P2") (pin "A") (pinfunction "A_A") (pintype "passive"))
      (node (ref "P3") (pin "A") (pinfunction "A_A") (pintype "passive"))
      (node (ref "P4") (pin "A") (pinfunction "A_A") (pintype "passive"))
      (node (ref "P6") (pin "A") (pinfunction "A_A") (pintype "passive"))
      (node (ref "P8") (pin "A") (pinfunction "A_A") (pintype "passive"))
      (node (ref "R23") (pin "2") (pinfunction "1_2") (pintype "passive"))
      (node (ref "R29") (pin "2") (pinfunction "1_2") (pintype "passive"))
      (node (ref "R38") (pin "2") (pinfunction "1_2") (pintype "passive"))
      (node (ref "R39") (pin "2") (pinfunction "1_2") (pintype "passive"))
      (node (ref "R40") (pin "2") (pinfunction "1_2") (pintype "passive"))
      (node (ref "R41") (pin "2") (pinfunction "1_2") (pintype "passive"))
      (node (ref "R46") (pin "2") (pinfunction "1_2") (pintype "passive"))
      (node (ref "R47") (pin "2") (pinfunction "1_2") (pintype "passive"))
      (node (ref "R48") (pin "2") (pinfunction "1_2") (pintype "passive"))
      (node (ref "R49") (pin "2") (pinfunction "1_2") (pintype "passive"))
      (node (ref "R50") (pin "2") (pinfunction "1_2") (pintype "passive"))
      (node (ref "R51") (pin "2") (pinfunction "1_2") (pintype "passive"))
      (node (ref "R52") (pin "2") (pinfunction "1_2") (pintype "passive"))
      (node (ref "R53") (pin "2") (pinfunction "1_2") (pintype "passive"))
      (node (ref "R55") (pin "1") (pinfunction "2_1") (pintype "passive"))
      (node (ref "R56") (pin "A") (pinfunction "A_A") (pintype "passive"))
      (node (ref "R57") (pin "A") (pinfunction "A_A") (pintype "passive"))
      (node (ref "R69") (pin "2") (pinfunction "1_2") (pintype "passive"))
      (node (ref "R70") (pin "2") (pinfunction "1_2") (pintype "passive"))
      (node (ref "R71") (pin "2") (pinfunction "1_2") (pintype "passive"))
      (node (ref "R72") (pin "2") (pinfunction "1_2") (pintype "passive"))
      (node (ref "R74") (pin "A") (pinfunction "A_A") (pintype "passive"))
      (node (ref "S1") (pin "T3") (pinfunction "NO1_T3") (pintype "bidirectional"))
      (node (ref "S10") (pin "T3") (pinfunction "NO1_T3") (pintype "bidirectional"))
      (node (ref "S11") (pin "T3") (pinfunction "NO1_T3") (pintype "bidirectional"))
      (node (ref "S12") (pin "T3") (pinfunction "NO1_T3") (pintype "bidirectional"))
      (node (ref "S13") (pin "T3") (pinfunction "NO1_T3") (pintype "bidirectional"))
      (node (ref "S14") (pin "T3") (pinfunction "NO1_T3") (pintype "bidirectional"))
      (node (ref "S15") (pin "T3") (pinfunction "NO1_T3") (pintype "bidirectional"))
      (node (ref "S16") (pin "T3") (pinfunction "NO1_T3") (pintype "bidirectional"))
      (node (ref "S2") (pin "T3") (pinfunction "NO1_T3") (pintype "bidirectional"))
      (node (ref "S3") (pin "T3") (pinfunction "NO1_T3") (pintype "bidirectional"))
      (node (ref "S4") (pin "T3") (pinfunction "NO1_T3") (pintype "bidirectional"))
      (node (ref "S5") (pin "T3") (pinfunction "NO1_T3") (pintype "bidirectional"))
      (node (ref "S6") (pin "T3") (pinfunction "NO1_T3") (pintype "bidirectional"))
      (node (ref "S7") (pin "T3") (pinfunction "NO1_T3") (pintype "bidirectional"))
      (node (ref "S8") (pin "T3") (pinfunction "NO1_T3") (pintype "bidirectional"))
      (node (ref "S9") (pin "T3") (pinfunction "NO1_T3") (pintype "bidirectional"))
      (node (ref "X1") (pin "1") (pinfunction "1_1") (pintype "passive"))
    )
    (net (code "19") (name "LATCH") (class "Default")
      (node (ref "A1") (pin "22") (pinfunction "GP17_22") (pintype "bidirectional"))
      (node (ref "A15") (pin "6") (pinfunction "~{WR}_6") (pintype "bidirectional"))
      (node (ref "A15") (pin "8") (pinfunction "~{CS}_8") (pintype "bidirectional"))
      (node (ref "A29") (pin "2") (pinfunction "I_2") (pintype "input"))
      (node (ref "A7") (pin "6") (pinfunction "~{WR}_6") (pintype "bidirectional"))
      (node (ref "A7") (pin "8") (pinfunction "~{CS}_8") (pintype "bidirectional"))
    )
    (net (code "20") (name "LOAD") (class "Default")
      (node (ref "A1") (pin "34") (pinfunction "GP28_A2_34") (pintype "bidirectional"))
      (node (ref "A23") (pin "1") (pinfunction "SH/~{LD}_1") (pintype "input"))
      (node (ref "A24") (pin "1") (pinfunction "SH/~{LD}_1") (pintype "input"))
    )
    (net (code "21") (name "Net-(A1-ADC_VREF)") (class "Default")
      (node (ref "A1") (pin "35") (pinfunction "ADC_VREF_35") (pintype "bidirectional"))
      (node (ref "J1") (pin "1") (pinfunction "1_1") (pintype "passive"))
    )
    (net (code "22") (name "Net-(A1-GP6)") (class "Default")
      (node (ref "A1") (pin "9") (pinfunction "GP6_9") (pintype "bidirectional"))
      (node (ref "JP1") (pin "1") (pinfunction "1_1") (pintype "passive"))
    )
    (net (code "23") (name "Net-(A1-GP7)") (class "Default")
      (node (ref "A1") (pin "10") (pinfunction "GP7_10") (pintype "bidirectional"))
      (node (ref "JP1") (pin "2") (pinfunction "2_2") (pintype "passive"))
    )
    (net (code "24") (name "Net-(A2A-I)") (class "Default")
      (node (ref "A2") (pin "11") (pinfunction "I_11") (pintype "input"))
      (node (ref "A2") (pin "13") (pinfunction "I_13") (pintype "input"))
      (node (ref "A2") (pin "2") (pinfunction "O_2") (pintype "output"))
      (node (ref "A2") (pin "9") (pinfunction "I_9") (pintype "input"))
    )
    (net (code "25") (name "Net-(A2A-O)") (class "Default")
      (node (ref "A2") (pin "10") (pinfunction "O_10") (pintype "output"))
      (node (ref "A2") (pin "12") (pinfunction "O_12") (pintype "output"))
      (node (ref "A2") (pin "8") (pinfunction "O_8") (pintype "output"))
      (node (ref "R78") (pin "2") (pinfunction "1_2") (pintype "passive"))
    )
    (net (code "26") (name "Net-(A2E-I)") (class "Default")
      (node (ref "A2") (pin "3") (pinfunction "I_3") (pintype "input"))
      (node (ref "OK1") (pin "4") (pinfunction "COL_4") (pintype "passive"))
      (node (ref "R65") (pin "2") (pinfunction "1_2") (pintype "passive"))
    )
    (net (code "27") (name "Net-(A2E-O)") (class "Default")
      (node (ref "A2") (pin "4") (pinfunction "O_4") (pintype "output"))
      (node (ref "A2") (pin "5") (pinfunction "I_5") (pintype "input"))
    )
    (net (code "28") (name "Net-(A3-VI)") (class "Default")
      (node (ref "A3") (pin "1") (pinfunction "VI_1") (pintype "input"))
      (node (ref "C59") (pin "2") (pinfunction "2_2") (pintype "passive"))
      (node (ref "J2") (pin "1") (pinfunction "1_1") (pintype "passive"))
    )
    (net (code "29") (name "Net-(A4B-I)") (class "Default")
      (node (ref "A4") (pin "11") (pinfunction "I_11") (pintype "input"))
      (node (ref "C74") (pin "2") (pinfunction "2_2") (pintype "passive"))
      (node (ref "Q13") (pin "1") (pinfunction "1_1") (pintype "passive"))
      (node (ref "R59") (pin "2") (pinfunction "1_2") (pintype "passive"))
    )
    (net (code "30") (name "Net-(A4B-O)") (class "Default")
      (node (ref "A4") (pin "10") (pinfunction "O_10") (pintype "output"))
      (node (ref "A4") (pin "9") (pinfunction "I_9") (pintype "input"))
      (node (ref "R59") (pin "1") (pinfunction "2_1") (pintype "passive"))
      (node (ref "R60") (pin "1") (pinfunction "2_1") (pintype "passive"))
    )
    (net (code "31") (name "Net-(A4D-I)") (class "Default")
      (node (ref "A4") (pin "1") (pinfunction "I_1") (pintype "input"))
      (node (ref "C65") (pin "2") (pinfunction "2_2") (pintype "passive"))
      (node (ref "R43") (pin "2") (pinfunction "1_2") (pintype "passive"))
    )
    (net (code "32") (name "Net-(A4D-O)") (class "Default")
      (node (ref "A4") (pin "2") (pinfunction "O_2") (pintype "output"))
      (node (ref "A4") (pin "3") (pinfunction "I_3") (pintype "input"))
      (node (ref "A4") (pin "5") (pinfunction "I_5") (pintype "input"))
      (node (ref "A5") (pin "1") (pinfunction "I_1") (pintype "input"))
      (node (ref "A5") (pin "11") (pinfunction "I_11") (pintype "input"))
      (node (ref "A5") (pin "13") (pinfunction "I_13") (pintype "input"))
      (node (ref "A5") (pin "3") (pinfunction "I_3") (pintype "input"))
      (node (ref "A5") (pin "5") (pinfunction "I_5") (pintype "input"))
      (node (ref "A5") (pin "9") (pinfunction "I_9") (pintype "input"))
      (node (ref "R43") (pin "1") (pinfunction "2_1") (pintype "passive"))
    )
    (net (code "33") (name "Net-(A4E-O)") (class "Default")
      (node (ref "A4") (pin "4") (pinfunction "O_4") (pintype "output"))
      (node (ref "A4") (pin "6") (pinfunction "O_6") (pintype "output"))
      (node (ref "A5") (pin "10") (pinfunction "O_10") (pintype "output"))
      (node (ref "A5") (pin "12") (pinfunction "O_12") (pintype "output"))
      (node (ref "A5") (pin "2") (pinfunction "O_2") (pintype "output"))
      (node (ref "A5") (pin "4") (pinfunction "O_4") (pintype "output"))
      (node (ref "A5") (pin "6") (pinfunction "O_6") (pintype "output"))
      (node (ref "A5") (pin "8") (pinfunction "O_8") (pintype "output"))
      (node (ref "C66") (pin "2") (pinfunction "2_2") (pintype "passive"))
      (node (ref "C67") (pin "2") (pinfunction "2_2") (pintype "passive"))
    )
    (net (code "34") (name "Net-(A6A-QA)") (class "Default")
      (node (ref "A6") (pin "15") (pinfunction "QA_15") (pintype "tri_state"))
      (node (ref "A7") (pin "10") (pinfunction "D0_10") (pintype "bidirectional"))
    )
    (net (code "35") (name "Net-(A6A-QB)") (class "Default")
      (node (ref "A6") (pin "1") (pinfunction "QB_1") (pintype "tri_state"))
      (node (ref "A7") (pin "11") (pinfunction "D1_11") (pintype "bidirectional"))
    )
    (net (code "36") (name "Net-(A6A-QC)") (class "Default")
      (node (ref "A6") (pin "2") (pinfunction "QC_2") (pintype "tri_state"))
      (node (ref "A7") (pin "13") (pinfunction "D2_13") (pintype "bidirectional"))
    )
    (net (code "37") (name "Net-(A6A-QD)") (class "Default")
      (node (ref "A6") (pin "3") (pinfunction "QD_3") (pintype "tri_state"))
      (node (ref "A7") (pin "14") (pinfunction "D3_14") (pintype "bidirectional"))
    )
    (net (code "38") (name "Net-(A6A-QE)") (class "Default")
      (node (ref "A6") (pin "4") (pinfunction "QE_4") (pintype "tri_state"))
      (node (ref "A7") (pin "15") (pinfunction "D4_15") (pintype "bidirectional"))
    )
    (net (code "39") (name "Net-(A6A-QF)") (class "Default")
      (node (ref "A6") (pin "5") (pinfunction "QF_5") (pintype "tri_state"))
      (node (ref "A7") (pin "16") (pinfunction "D5_16") (pintype "bidirectional"))
    )
    (net (code "40") (name "Net-(A6A-QG)") (class "Default")
      (node (ref "A6") (pin "6") (pinfunction "QG_6") (pintype "tri_state"))
      (node (ref "A7") (pin "17") (pinfunction "D6_17") (pintype "bidirectional"))
    )
    (net (code "41") (name "Net-(A6A-QH)") (class "Default")
      (node (ref "A6") (pin "7") (pinfunction "QH_7") (pintype "tri_state"))
      (node (ref "A7") (pin "18") (pinfunction "D7_18") (pintype "bidirectional"))
    )
    (net (code "42") (name "Net-(A7-DOAB)") (class "Default")
      (node (ref "A7") (pin "21") (pinfunction "DOAB_21") (pintype "bidirectional"))
      (node (ref "A8") (pin "4") (pinfunction "DIN_4") (pintype "bidirectional"))
    )
    (net (code "43") (name "Net-(A7-DOCD)") (class "Default")
      (node (ref "A7") (pin "22") (pinfunction "DOCD_22") (pintype "bidirectional"))
      (node (ref "A9") (pin "4") (pinfunction "DIN_4") (pintype "bidirectional"))
    )
    (net (code "44") (name "Net-(A7-SMPAC)") (class "Default")
      (node (ref "A7") (pin "20") (pinfunction "SMPAC_20") (pintype "bidirectional"))
      (node (ref "A8") (pin "8") (pinfunction "SMP1_8") (pintype "bidirectional"))
      (node (ref "A9") (pin "8") (pinfunction "SMP1_8") (pintype "bidirectional"))
    )
    (net (code "45") (name "Net-(A7-SMPBD)") (class "Default")
      (node (ref "A7") (pin "19") (pinfunction "SMPBD_19") (pintype "bidirectional"))
      (node (ref "A8") (pin "7") (pinfunction "SMP2_7") (pintype "bidirectional"))
      (node (ref "A9") (pin "7") (pinfunction "SMP2_7") (pintype "bidirectional"))
    )
    (net (code "46") (name "Net-(A7-ØSY)") (class "Default")
      (node (ref "A7") (pin "23") (pinfunction "ØSY_23") (pintype "bidirectional"))
      (node (ref "A8") (pin "5") (pinfunction "CLK_5") (pintype "bidirectional"))
      (node (ref "A9") (pin "5") (pinfunction "CLK_5") (pintype "bidirectional"))
    )
    (net (code "47") (name "Net-(A8-SWIN)") (class "Default")
      (node (ref "A8") (pin "12") (pinfunction "SWIN_12") (pintype "bidirectional"))
      (node (ref "R34") (pin "2") (pinfunction "1_2") (pintype "passive"))
    )
    (net (code "48") (name "Net-(A9-SWIN)") (class "Default")
      (node (ref "A9") (pin "12") (pinfunction "SWIN_12") (pintype "bidirectional"))
      (node (ref "R17") (pin "2") (pinfunction "1_2") (pintype "passive"))
    )
    (net (code "49") (name "Net-(A10A-+IN)") (class "Default")
      (node (ref "A10") (pin "3") (pinfunction "+IN_3") (pintype "input"))
      (node (ref "A8") (pin "16") (pinfunction "CV_16") (pintype "bidirectional"))
      (node (ref "C50") (pin "2") (pinfunction "2_2") (pintype "passive"))
    )
    (net (code "50") (name "Net-(A10A--IN)") (class "Default")
      (node (ref "A10") (pin "1") (pinfunction "OUT_1") (pintype "output"))
      (node (ref "A10") (pin "2") (pinfunction "-IN_2") (pintype "input"))
      (node (ref "A8") (pin "14") (pinfunction "MP_14") (pintype "bidirectional"))
    )
    (net (code "51") (name "Net-(A10B-+IN)") (class "Default")
      (node (ref "A10") (pin "5") (pinfunction "+IN_5") (pintype "input"))
      (node (ref "A8") (pin "13") (pinfunction "AOUT_13") (pintype "bidirectional"))
      (node (ref "C42") (pin "2") (pinfunction "2_2") (pintype "passive"))
    )
    (net (code "52") (name "Net-(A10B--IN)") (class "Default")
      (node (ref "A10") (pin "6") (pinfunction "-IN_6") (pintype "input"))
      (node (ref "A10") (pin "7") (pinfunction "OUT_7") (pintype "output"))
      (node (ref "R34") (pin "1") (pinfunction "2_1") (pintype "passive"))
    )
    (net (code "53") (name "Net-(A11A-+IN)") (class "Default")
      (node (ref "A11") (pin "3") (pinfunction "+IN_3") (pintype "input"))
      (node (ref "A8") (pin "11") (pinfunction "CH2_11") (pintype "bidirectional"))
      (node (ref "C25") (pin "2") (pinfunction "2_2") (pintype "passive"))
    )
    (net (code "54") (name "Net-(A11A--IN)") (class "Default")
      (node (ref "A11") (pin "1") (pinfunction "OUT_1") (pintype "output"))
      (node (ref "A11") (pin "2") (pinfunction "-IN_2") (pintype "input"))
      (node (ref "R36") (pin "2") (pinfunction "1_2") (pintype "passive"))
    )
    (net (code "55") (name "Net-(A11B-+IN)") (class "Default")
      (node (ref "A11") (pin "5") (pinfunction "+IN_5") (pintype "input"))
      (node (ref "A8") (pin "10") (pinfunction "CH1_10") (pintype "bidirectional"))
      (node (ref "C26") (pin "2") (pinfunction "2_2") (pintype "passive"))
    )
    (net (code "56") (name "Net-(A11B--IN)") (class "Default")
      (node (ref "A11") (pin "6") (pinfunction "-IN_6") (pintype "input"))
      (node (ref "A11") (pin "7") (pinfunction "OUT_7") (pintype "output"))
      (node (ref "R35") (pin "2") (pinfunction "1_2") (pintype "passive"))
    )
    (net (code "57") (name "Net-(A12A-+IN)") (class "Default")
      (node (ref "A12") (pin "3") (pinfunction "+IN_3") (pintype "input"))
      (node (ref "A9") (pin "16") (pinfunction "CV_16") (pintype "bidirectional"))
      (node (ref "C51") (pin "2") (pinfunction "2_2") (pintype "passive"))
    )
    (net (code "58") (name "Net-(A12A--IN)") (class "Default")
      (node (ref "A12") (pin "1") (pinfunction "OUT_1") (pintype "output"))
      (node (ref "A12") (pin "2") (pinfunction "-IN_2") (pintype "input"))
      (node (ref "A9") (pin "14") (pinfunction "MP_14") (pintype "bidirectional"))
    )
    (net (code "59") (name "Net-(A12B-+IN)") (class "Default")
      (node (ref "A12") (pin "5") (pinfunction "+IN_5") (pintype "input"))
      (node (ref "A9") (pin "13") (pinfunction "AOUT_13") (pintype "bidirectional"))
      (node (ref "C37") (pin "2") (pinfunction "2_2") (pintype "passive"))
    )
    (net (code "60") (name "Net-(A12B--IN)") (class "Default")
      (node (ref "A12") (pin "6") (pinfunction "-IN_6") (pintype "input"))
      (node (ref "A12") (pin "7") (pinfunction "OUT_7") (pintype "output"))
      (node (ref "R17") (pin "1") (pinfunction "2_1") (pintype "passive"))
    )
    (net (code "61") (name "Net-(A13A-+IN)") (class "Default")
      (node (ref "A13") (pin "3") (pinfunction "+IN_3") (pintype "input"))
      (node (ref "A9") (pin "11") (pinfunction "CH2_11") (pintype "bidirectional"))
      (node (ref "C35") (pin "2") (pinfunction "2_2") (pintype "passive"))
    )
    (net (code "62") (name "Net-(A13A--IN)") (class "Default")
      (node (ref "A13") (pin "1") (pinfunction "OUT_1") (pintype "output"))
      (node (ref "A13") (pin "2") (pinfunction "-IN_2") (pintype "input"))
      (node (ref "R24") (pin "2") (pinfunction "1_2") (pintype "passive"))
    )
    (net (code "63") (name "Net-(A13B-+IN)") (class "Default")
      (node (ref "A13") (pin "5") (pinfunction "+IN_5") (pintype "input"))
      (node (ref "A9") (pin "10") (pinfunction "CH1_10") (pintype "bidirectional"))
      (node (ref "C27") (pin "2") (pinfunction "2_2") (pintype "passive"))
    )
    (net (code "64") (name "Net-(A13B--IN)") (class "Default")
      (node (ref "A13") (pin "6") (pinfunction "-IN_6") (pintype "input"))
      (node (ref "A13") (pin "7") (pinfunction "OUT_7") (pintype "output"))
      (node (ref "R19") (pin "2") (pinfunction "1_2") (pintype "passive"))
    )
    (net (code "65") (name "Net-(A14A-QA)") (class "Default")
      (node (ref "A14") (pin "15") (pinfunction "QA_15") (pintype "tri_state"))
      (node (ref "A15") (pin "10") (pinfunction "D0_10") (pintype "bidirectional"))
    )
    (net (code "66") (name "Net-(A14A-QB)") (class "Default")
      (node (ref "A14") (pin "1") (pinfunction "QB_1") (pintype "tri_state"))
      (node (ref "A15") (pin "11") (pinfunction "D1_11") (pintype "bidirectional"))
    )
    (net (code "67") (name "Net-(A14A-QC)") (class "Default")
      (node (ref "A14") (pin "2") (pinfunction "QC_2") (pintype "tri_state"))
      (node (ref "A15") (pin "13") (pinfunction "D2_13") (pintype "bidirectional"))
    )
    (net (code "68") (name "Net-(A14A-QD)") (class "Default")
      (node (ref "A14") (pin "3") (pinfunction "QD_3") (pintype "tri_state"))
      (node (ref "A15") (pin "14") (pinfunction "D3_14") (pintype "bidirectional"))
    )
    (net (code "69") (name "Net-(A14A-QE)") (class "Default")
      (node (ref "A14") (pin "4") (pinfunction "QE_4") (pintype "tri_state"))
      (node (ref "A15") (pin "15") (pinfunction "D4_15") (pintype "bidirectional"))
    )
    (net (code "70") (name "Net-(A14A-QF)") (class "Default")
      (node (ref "A14") (pin "5") (pinfunction "QF_5") (pintype "tri_state"))
      (node (ref "A15") (pin "16") (pinfunction "D5_16") (pintype "bidirectional"))
    )
    (net (code "71") (name "Net-(A14A-QG)") (class "Default")
      (node (ref "A14") (pin "6") (pinfunction "QG_6") (pintype "tri_state"))
      (node (ref "A15") (pin "17") (pinfunction "D6_17") (pintype "bidirectional"))
    )
    (net (code "72") (name "Net-(A14A-QH)") (class "Default")
      (node (ref "A14") (pin "7") (pinfunction "QH_7") (pintype "tri_state"))
      (node (ref "A15") (pin "18") (pinfunction "D7_18") (pintype "bidirectional"))
    )
    (net (code "73") (name "Net-(A14A-QH*)") (class "Default")
      (node (ref "A14") (pin "9") (pinfunction "QH*_9") (pintype "tri_state"))
      (node (ref "A6") (pin "14") (pinfunction "SER_14") (pintype "input"))
    )
    (net (code "74") (name "Net-(A14A-RCK)") (class "Default")
      (node (ref "A14") (pin "12") (pinfunction "RCK_12") (pintype "input"))
      (node (ref "A29") (pin "4") (pinfunction "O_4") (pintype "output"))
      (node (ref "A6") (pin "12") (pinfunction "RCK_12") (pintype "input"))
    )
    (net (code "75") (name "Net-(A15-DOAB)") (class "Default")
      (node (ref "A15") (pin "21") (pinfunction "DOAB_21") (pintype "bidirectional"))
      (node (ref "A16") (pin "4") (pinfunction "DIN_4") (pintype "bidirectional"))
    )
    (net (code "76") (name "Net-(A15-DOCD)") (class "Default")
      (node (ref "A15") (pin "22") (pinfunction "DOCD_22") (pintype "bidirectional"))
      (node (ref "A17") (pin "4") (pinfunction "DIN_4") (pintype "bidirectional"))
    )
    (net (code "77") (name "Net-(A15-SMPAC)") (class "Default")
      (node (ref "A15") (pin "20") (pinfunction "SMPAC_20") (pintype "bidirectional"))
      (node (ref "A16") (pin "8") (pinfunction "SMP1_8") (pintype "bidirectional"))
      (node (ref "A17") (pin "8") (pinfunction "SMP1_8") (pintype "bidirectional"))
    )
    (net (code "78") (name "Net-(A15-SMPBD)") (class "Default")
      (node (ref "A15") (pin "19") (pinfunction "SMPBD_19") (pintype "bidirectional"))
      (node (ref "A16") (pin "7") (pinfunction "SMP2_7") (pintype "bidirectional"))
      (node (ref "A17") (pin "7") (pinfunction "SMP2_7") (pintype "bidirectional"))
    )
    (net (code "79") (name "Net-(A15-ØSY)") (class "Default")
      (node (ref "A15") (pin "23") (pinfunction "ØSY_23") (pintype "bidirectional"))
      (node (ref "A16") (pin "5") (pinfunction "CLK_5") (pintype "bidirectional"))
      (node (ref "A17") (pin "5") (pinfunction "CLK_5") (pintype "bidirectional"))
    )
    (net (code "80") (name "Net-(A16-AOUT)") (class "Default")
      (node (ref "A16") (pin "13") (pinfunction "AOUT_13") (pintype "bidirectional"))
      (node (ref "A18") (pin "5") (pinfunction "+IN_5") (pintype "input"))
      (node (ref "C49") (pin "2") (pinfunction "2_2") (pintype "passive"))
    )
    (net (code "81") (name "Net-(A16-CH1)") (class "Default")
      (node (ref "A16") (pin "10") (pinfunction "CH1_10") (pintype "bidirectional"))
      (node (ref "A19") (pin "5") (pinfunction "+IN_5") (pintype "input"))
      (node (ref "C21") (pin "2") (pinfunction "2_2") (pintype "passive"))
    )
    (net (code "82") (name "Net-(A16-CH2)") (class "Default")
      (node (ref "A16") (pin "11") (pinfunction "CH2_11") (pintype "bidirectional"))
      (node (ref "A19") (pin "3") (pinfunction "+IN_3") (pintype "input"))
      (node (ref "C22") (pin "2") (pinfunction "2_2") (pintype "passive"))
    )
    (net (code "83") (name "Net-(A16-CV)") (class "Default")
      (node (ref "A16") (pin "16") (pinfunction "CV_16") (pintype "bidirectional"))
      (node (ref "A18") (pin "3") (pinfunction "+IN_3") (pintype "input"))
      (node (ref "C36") (pin "2") (pinfunction "2_2") (pintype "passive"))
    )
    (net (code "84") (name "Net-(A16-MP)") (class "Default")
      (node (ref "A16") (pin "14") (pinfunction "MP_14") (pintype "bidirectional"))
      (node (ref "A18") (pin "1") (pinfunction "OUT_1") (pintype "output"))
      (node (ref "A18") (pin "2") (pinfunction "-IN_2") (pintype "input"))
    )
    (net (code "85") (name "Net-(A16-SWIN)") (class "Default")
      (node (ref "A16") (pin "12") (pinfunction "SWIN_12") (pintype "bidirectional"))
      (node (ref "R58") (pin "2") (pinfunction "1_2") (pintype "passive"))
    )
    (net (code "86") (name "Net-(A17-AOUT)") (class "Default")
      (node (ref "A17") (pin "13") (pinfunction "AOUT_13") (pintype "bidirectional"))
      (node (ref "A20") (pin "5") (pinfunction "+IN_5") (pintype "input"))
      (node (ref "C43") (pin "2") (pinfunction "2_2") (pintype "passive"))
    )
    (net (code "87") (name "Net-(A17-CH1)") (class "Default")
      (node (ref "A17") (pin "10") (pinfunction "CH1_10") (pintype "bidirectional"))
      (node (ref "A21") (pin "5") (pinfunction "+IN_5") (pintype "input"))
      (node (ref "C24") (pin "2") (pinfunction "2_2") (pintype "passive"))
    )
    (net (code "88") (name "Net-(A17-CH2)") (class "Default")
      (node (ref "A17") (pin "11") (pinfunction "CH2_11") (pintype "bidirectional"))
      (node (ref "A21") (pin "3") (pinfunction "+IN_3") (pintype "input"))
      (node (ref "C23") (pin "2") (pinfunction "2_2") (pintype "passive"))
    )
    (net (code "89") (name "Net-(A17-CV)") (class "Default")
      (node (ref "A17") (pin "16") (pinfunction "CV_16") (pintype "bidirectional"))
      (node (ref "A20") (pin "3") (pinfunction "+IN_3") (pintype "input"))
      (node (ref "C45") (pin "2") (pinfunction "2_2") (pintype "passive"))
    )
    (net (code "90") (name "Net-(A17-MP)") (class "Default")
      (node (ref "A17") (pin "14") (pinfunction "MP_14") (pintype "bidirectional"))
      (node (ref "A20") (pin "1") (pinfunction "OUT_1") (pintype "output"))
      (node (ref "A20") (pin "2") (pinfunction "-IN_2") (pintype "input"))
    )
    (net (code "91") (name "Net-(A17-SWIN)") (class "Default")
      (node (ref "A17") (pin "12") (pinfunction "SWIN_12") (pintype "bidirectional"))
      (node (ref "R37") (pin "2") (pinfunction "1_2") (pintype "passive"))
    )
    (net (code "92") (name "Net-(A18B--IN)") (class "Default")
      (node (ref "A18") (pin "6") (pinfunction "-IN_6") (pintype "input"))
      (node (ref "A18") (pin "7") (pinfunction "OUT_7") (pintype "output"))
      (node (ref "R58") (pin "1") (pinfunction "2_1") (pintype "passive"))
    )
    (net (code "93") (name "Net-(A19A--IN)") (class "Default")
      (node (ref "A19") (pin "1") (pinfunction "OUT_1") (pintype "output"))
      (node (ref "A19") (pin "2") (pinfunction "-IN_2") (pintype "input"))
      (node (ref "R66") (pin "2") (pinfunction "1_2") (pintype "passive"))
    )
    (net (code "94") (name "Net-(A19B--IN)") (class "Default")
      (node (ref "A19") (pin "6") (pinfunction "-IN_6") (pintype "input"))
      (node (ref "A19") (pin "7") (pinfunction "OUT_7") (pintype "output"))
      (node (ref "R62") (pin "2") (pinfunction "1_2") (pintype "passive"))
    )
    (net (code "95") (name "Net-(A20B--IN)") (class "Default")
      (node (ref "A20") (pin "6") (pinfunction "-IN_6") (pintype "input"))
      (node (ref "A20") (pin "7") (pinfunction "OUT_7") (pintype "output"))
      (node (ref "R37") (pin "1") (pinfunction "2_1") (pintype "passive"))
    )
    (net (code "96") (name "Net-(A21A--IN)") (class "Default")
      (node (ref "A21") (pin "1") (pinfunction "OUT_1") (pintype "output"))
      (node (ref "A21") (pin "2") (pinfunction "-IN_2") (pintype "input"))
      (node (ref "R44") (pin "2") (pinfunction "1_2") (pintype "passive"))
    )
    (net (code "97") (name "Net-(A21B--IN)") (class "Default")
      (node (ref "A21") (pin "6") (pinfunction "-IN_6") (pintype "input"))
      (node (ref "A21") (pin "7") (pinfunction "OUT_7") (pintype "output"))
      (node (ref "R42") (pin "2") (pinfunction "1_2") (pintype "passive"))
    )
    (net (code "98") (name "Net-(A22A-+IN)") (class "Default")
      (node (ref "A22") (pin "3") (pinfunction "+IN_3") (pintype "input"))
      (node (ref "C41") (pin "2") (pinfunction "2_2") (pintype "passive"))
      (node (ref "R22") (pin "1") (pinfunction "2_1") (pintype "passive"))
    )
    (net (code "99") (name "Net-(A22A--IN)") (class "Default")
      (node (ref "A22") (pin "1") (pinfunction "OUT_1") (pintype "output"))
      (node (ref "A22") (pin "2") (pinfunction "-IN_2") (pintype "input"))
      (node (ref "C44") (pin "1") (pinfunction "1_1") (pintype "passive"))
      (node (ref "R21") (pin "2") (pinfunction "1_2") (pintype "passive"))
    )
    (net (code "100") (name "Net-(A22B-+IN)") (class "Default")
      (node (ref "A22") (pin "5") (pinfunction "+IN_5") (pintype "input"))
      (node (ref "C39") (pin "2") (pinfunction "2_2") (pintype "passive"))
      (node (ref "R27") (pin "1") (pinfunction "2_1") (pintype "passive"))
    )
    (net (code "101") (name "Net-(A22B--IN)") (class "Default")
      (node (ref "A22") (pin "6") (pinfunction "-IN_6") (pintype "input"))
      (node (ref "A22") (pin "7") (pinfunction "OUT_7") (pintype "output"))
      (node (ref "C48") (pin "1") (pinfunction "1_1") (pintype "passive"))
      (node (ref "R28") (pin "2") (pinfunction "1_2") (pintype "passive"))
    )
    (net (code "102") (name "Net-(A23A-A)") (class "Default")
      (node (ref "A23") (pin "11") (pinfunction "A_11") (pintype "input"))
      (node (ref "C1") (pin "2") (pinfunction "2_2") (pintype "passive"))
      (node (ref "R1") (pin "2") (pinfunction "1_2") (pintype "passive"))
      (node (ref "S1") (pin "T2") (pinfunction "COM2_T2") (pintype "bidirectional"))
    )
    (net (code "103") (name "Net-(A23A-B)") (class "Default")
      (node (ref "A23") (pin "12") (pinfunction "B_12") (pintype "input"))
      (node (ref "C2") (pin "2") (pinfunction "2_2") (pintype "passive"))
      (node (ref "R2") (pin "2") (pinfunction "1_2") (pintype "passive"))
      (node (ref "S2") (pin "T2") (pinfunction "COM2_T2") (pintype "bidirectional"))
    )
    (net (code "104") (name "Net-(A23A-C)") (class "Default")
      (node (ref "A23") (pin "13") (pinfunction "C_13") (pintype "input"))
      (node (ref "C3") (pin "2") (pinfunction "2_2") (pintype "passive"))
      (node (ref "R3") (pin "2") (pinfunction "1_2") (pintype "passive"))
      (node (ref "S3") (pin "T2") (pinfunction "COM2_T2") (pintype "bidirectional"))
    )
    (net (code "105") (name "Net-(A23A-D)") (class "Default")
      (node (ref "A23") (pin "14") (pinfunction "D_14") (pintype "input"))
      (node (ref "C4") (pin "2") (pinfunction "2_2") (pintype "passive"))
      (node (ref "R4") (pin "2") (pinfunction "1_2") (pintype "passive"))
      (node (ref "S4") (pin "T2") (pinfunction "COM2_T2") (pintype "bidirectional"))
    )
    (net (code "106") (name "Net-(A23A-E)") (class "Default")
      (node (ref "A23") (pin "3") (pinfunction "E_3") (pintype "input"))
      (node (ref "C8") (pin "2") (pinfunction "2_2") (pintype "passive"))
      (node (ref "R8") (pin "2") (pinfunction "1_2") (pintype "passive"))
      (node (ref "S8") (pin "T2") (pinfunction "COM2_T2") (pintype "bidirectional"))
    )
    (net (code "107") (name "Net-(A23A-F)") (class "Default")
      (node (ref "A23") (pin "4") (pinfunction "F_4") (pintype "input"))
      (node (ref "C7") (pin "2") (pinfunction "2_2") (pintype "passive"))
      (node (ref "R7") (pin "2") (pinfunction "1_2") (pintype "passive"))
      (node (ref "S7") (pin "T2") (pinfunction "COM2_T2") (pintype "bidirectional"))
    )
    (net (code "108") (name "Net-(A23A-G)") (class "Default")
      (node (ref "A23") (pin "5") (pinfunction "G_5") (pintype "input"))
      (node (ref "C6") (pin "2") (pinfunction "2_2") (pintype "passive"))
      (node (ref "R6") (pin "2") (pinfunction "1_2") (pintype "passive"))
      (node (ref "S6") (pin "T2") (pinfunction "COM2_T2") (pintype "bidirectional"))
    )
    (net (code "109") (name "Net-(A23A-H)") (class "Default")
      (node (ref "A23") (pin "6") (pinfunction "H_6") (pintype "input"))
      (node (ref "C5") (pin "2") (pinfunction "2_2") (pintype "passive"))
      (node (ref "R5") (pin "2") (pinfunction "1_2") (pintype "passive"))
      (node (ref "S5") (pin "T2") (pinfunction "COM2_T2") (pintype "bidirectional"))
    )
    (net (code "110") (name "Net-(A23A-QH)") (class "Default")
      (node (ref "A23") (pin "9") (pinfunction "QH_9") (pintype "output"))
      (node (ref "A24") (pin "10") (pinfunction "SER_10") (pintype "input"))
    )
    (net (code "111") (name "Net-(A24A-A)") (class "Default")
      (node (ref "A24") (pin "11") (pinfunction "A_11") (pintype "input"))
      (node (ref "C9") (pin "2") (pinfunction "2_2") (pintype "passive"))
      (node (ref "R9") (pin "2") (pinfunction "1_2") (pintype "passive"))
      (node (ref "S9") (pin "T2") (pinfunction "COM2_T2") (pintype "bidirectional"))
    )
    (net (code "112") (name "Net-(A24A-B)") (class "Default")
      (node (ref "A24") (pin "12") (pinfunction "B_12") (pintype "input"))
      (node (ref "C10") (pin "2") (pinfunction "2_2") (pintype "passive"))
      (node (ref "R10") (pin "2") (pinfunction "1_2") (pintype "passive"))
      (node (ref "S10") (pin "T2") (pinfunction "COM2_T2") (pintype "bidirectional"))
    )
    (net (code "113") (name "Net-(A24A-C)") (class "Default")
      (node (ref "A24") (pin "13") (pinfunction "C_13") (pintype "input"))
      (node (ref "C11") (pin "2") (pinfunction "2_2") (pintype "passive"))
      (node (ref "R11") (pin "2") (pinfunction "1_2") (pintype "passive"))
      (node (ref "S11") (pin "T2") (pinfunction "COM2_T2") (pintype "bidirectional"))
    )
    (net (code "114") (name "Net-(A24A-D)") (class "Default")
      (node (ref "A24") (pin "14") (pinfunction "D_14") (pintype "input"))
      (node (ref "C12") (pin "2") (pinfunction "2_2") (pintype "passive"))
      (node (ref "R12") (pin "2") (pinfunction "1_2") (pintype "passive"))
      (node (ref "S12") (pin "T2") (pinfunction "COM2_T2") (pintype "bidirectional"))
    )
    (net (code "115") (name "Net-(A24A-E)") (class "Default")
      (node (ref "A24") (pin "3") (pinfunction "E_3") (pintype "input"))
      (node (ref "C16") (pin "2") (pinfunction "2_2") (pintype "passive"))
      (node (ref "R16") (pin "2") (pinfunction "1_2") (pintype "passive"))
      (node (ref "S16") (pin "T2") (pinfunction "COM2_T2") (pintype "bidirectional"))
    )
    (net (code "116") (name "Net-(A24A-F)") (class "Default")
      (node (ref "A24") (pin "4") (pinfunction "F_4") (pintype "input"))
      (node (ref "C15") (pin "2") (pinfunction "2_2") (pintype "passive"))
      (node (ref "R15") (pin "2") (pinfunction "1_2") (pintype "passive"))
      (node (ref "S15") (pin "T2") (pinfunction "COM2_T2") (pintype "bidirectional"))
    )
    (net (code "117") (name "Net-(A24A-G)") (class "Default")
      (node (ref "A24") (pin "5") (pinfunction "G_5") (pintype "input"))
      (node (ref "C14") (pin "2") (pinfunction "2_2") (pintype "passive"))
      (node (ref "R14") (pin "2") (pinfunction "1_2") (pintype "passive"))
      (node (ref "S14") (pin "T2") (pinfunction "COM2_T2") (pintype "bidirectional"))
    )
    (net (code "118") (name "Net-(A24A-H)") (class "Default")
      (node (ref "A24") (pin "6") (pinfunction "H_6") (pintype "input"))
      (node (ref "C13") (pin "2") (pinfunction "2_2") (pintype "passive"))
      (node (ref "R13") (pin "2") (pinfunction "1_2") (pintype "passive"))
      (node (ref "S13") (pin "T2") (pinfunction "COM2_T2") (pintype "bidirectional"))
    )
    (net (code "119") (name "Net-(A25A-X)") (class "Default")
      (node (ref "A25") (pin "3") (pinfunction "X_3") (pintype "bidirectional"))
      (node (ref "A27") (pin "12") (pinfunction "X3_12") (pintype "bidirectional"))
    )
    (net (code "120") (name "Net-(A25A-X0)") (class "Default")
      (node (ref "A25") (pin "13") (pinfunction "X0_13") (pintype "bidirectional"))
      (node (ref "Q6") (pin "E") (pinfunction "E_E") (pintype "bidirectional"))
      (node (ref "R51") (pin "1") (pinfunction "2_1") (pintype "passive"))
    )
    (net (code "121") (name "Net-(A25A-X1)") (class "Default")
      (node (ref "A25") (pin "14") (pinfunction "X1_14") (pintype "bidirectional"))
      (node (ref "Q7") (pin "E") (pinfunction "E_E") (pintype "bidirectional"))
      (node (ref "R52") (pin "1") (pinfunction "2_1") (pintype "passive"))
    )
    (net (code "122") (name "Net-(A25A-X2)") (class "Default")
      (node (ref "A25") (pin "15") (pinfunction "X2_15") (pintype "bidirectional"))
      (node (ref "Q8") (pin "E") (pinfunction "E_E") (pintype "bidirectional"))
      (node (ref "R53") (pin "1") (pinfunction "2_1") (pintype "passive"))
    )
    (net (code "123") (name "Net-(A25A-X3)") (class "Default")
      (node (ref "A25") (pin "12") (pinfunction "X3_12") (pintype "bidirectional"))
      (node (ref "Q5") (pin "E") (pinfunction "E_E") (pintype "bidirectional"))
      (node (ref "R50") (pin "1") (pinfunction "2_1") (pintype "passive"))
    )
    (net (code "124") (name "Net-(A25A-X4)") (class "Default")
      (node (ref "A25") (pin "1") (pinfunction "X4_1") (pintype "bidirectional"))
      (node (ref "Q1") (pin "E") (pinfunction "E_E") (pintype "bidirectional"))
      (node (ref "R38") (pin "1") (pinfunction "2_1") (pintype "passive"))
    )
    (net (code "125") (name "Net-(A25A-X5)") (class "Default")
      (node (ref "A25") (pin "5") (pinfunction "X5_5") (pintype "bidirectional"))
      (node (ref "Q4") (pin "E") (pinfunction "E_E") (pintype "bidirectional"))
      (node (ref "R41") (pin "1") (pinfunction "2_1") (pintype "passive"))
    )
    (net (code "126") (name "Net-(A25A-X6)") (class "Default")
      (node (ref "A25") (pin "2") (pinfunction "X6_2") (pintype "bidirectional"))
      (node (ref "Q2") (pin "E") (pinfunction "E_E") (pintype "bidirectional"))
      (node (ref "R39") (pin "1") (pinfunction "2_1") (pintype "passive"))
    )
    (net (code "127") (name "Net-(A25A-X7)") (class "Default")
      (node (ref "A25") (pin "4") (pinfunction "X7_4") (pintype "bidirectional"))
      (node (ref "Q3") (pin "E") (pinfunction "E_E") (pintype "bidirectional"))
      (node (ref "R40") (pin "1") (pinfunction "2_1") (pintype "passive"))
    )
    (net (code "128") (name "Net-(A26A-X)") (class "Default")
      (node (ref "A26") (pin "3") (pinfunction "X_3") (pintype "bidirectional"))
      (node (ref "A27") (pin "13") (pinfunction "X0_13") (pintype "bidirectional"))
    )
    (net (code "129") (name "Net-(A26A-X0)") (class "Default")
      (node (ref "A26") (pin "13") (pinfunction "X0_13") (pintype "bidirectional"))
      (node (ref "Q12") (pin "E") (pinfunction "E_E") (pintype "bidirectional"))
      (node (ref "R72") (pin "1") (pinfunction "2_1") (pintype "passive"))
    )
    (net (code "130") (name "Net-(A26A-X1)") (class "Default")
      (node (ref "A26") (pin "14") (pinfunction "X1_14") (pintype "bidirectional"))
      (node (ref "Q11") (pin "E") (pinfunction "E_E") (pintype "bidirectional"))
      (node (ref "R71") (pin "1") (pinfunction "2_1") (pintype "passive"))
    )
    (net (code "131") (name "Net-(A26A-X2)") (class "Default")
      (node (ref "A26") (pin "15") (pinfunction "X2_15") (pintype "bidirectional"))
      (node (ref "Q10") (pin "E") (pinfunction "E_E") (pintype "bidirectional"))
      (node (ref "R70") (pin "1") (pinfunction "2_1") (pintype "passive"))
    )
    (net (code "132") (name "Net-(A26A-X3)") (class "Default")
      (node (ref "A26") (pin "12") (pinfunction "X3_12") (pintype "bidirectional"))
      (node (ref "Q9") (pin "E") (pinfunction "E_E") (pintype "bidirectional"))
      (node (ref "R69") (pin "1") (pinfunction "2_1") (pintype "passive"))
    )
    (net (code "133") (name "Net-(A26A-X4)") (class "Default")
      (node (ref "A26") (pin "1") (pinfunction "X4_1") (pintype "bidirectional"))
      (node (ref "P1") (pin "S") (pinfunction "S_S") (pintype "passive"))
    )
    (net (code "134") (name "Net-(A26A-X5)") (class "Default")
      (node (ref "A26") (pin "5") (pinfunction "X5_5") (pintype "bidirectional"))
      (node (ref "P4") (pin "S") (pinfunction "S_S") (pintype "passive"))
    )
    (net (code "135") (name "Net-(A26A-X6)") (class "Default")
      (node (ref "A26") (pin "2") (pinfunction "X6_2") (pintype "bidirectional"))
      (node (ref "P2") (pin "S") (pinfunction "S_S") (pintype "passive"))
    )
    (net (code "136") (name "Net-(A26A-X7)") (class "Default")
      (node (ref "A26") (pin "4") (pinfunction "X7_4") (pintype "bidirectional"))
      (node (ref "P3") (pin "S") (pinfunction "S_S") (pintype "passive"))
    )
    (net (code "137") (name "Net-(A27A-X1)") (class "Default")
      (node (ref "A27") (pin "14") (pinfunction "X1_14") (pintype "bidirectional"))
      (node (ref "R56") (pin "S") (pinfunction "S_S") (pintype "passive"))
    )
    (net (code "138") (name "Net-(A27A-X2)") (class "Default")
      (node (ref "A27") (pin "15") (pinfunction "X2_15") (pintype "bidirectional"))
      (node (ref "R57") (pin "S") (pinfunction "S_S") (pintype "passive"))
    )
    (net (code "139") (name "Net-(A27A-X4)") (class "Default")
      (node (ref "A27") (pin "1") (pinfunction "X4_1") (pintype "bidirectional"))
      (node (ref "R74") (pin "S") (pinfunction "S_S") (pintype "passive"))
    )
    (net (code "140") (name "Net-(A27A-X5)") (class "Default")
      (node (ref "A27") (pin "5") (pinfunction "X5_5") (pintype "bidirectional"))
      (node (ref "P10") (pin "S") (pinfunction "S_S") (pintype "passive"))
    )
    (net (code "141") (name "Net-(A27A-X6)") (class "Default")
      (node (ref "A27") (pin "2") (pinfunction "X6_2") (pintype "bidirectional"))
      (node (ref "P6") (pin "S") (pinfunction "S_S") (pintype "passive"))
    )
    (net (code "142") (name "Net-(A27A-X7)") (class "Default")
      (node (ref "A27") (pin "4") (pinfunction "X7_4") (pintype "bidirectional"))
      (node (ref "P8") (pin "S") (pinfunction "S_S") (pintype "passive"))
    )
    (net (code "143") (name "Net-(A28A--IN)") (class "Default")
      (node (ref "A28") (pin "2") (pinfunction "-IN_2") (pintype "input"))
      (node (ref "R45") (pin "2") (pinfunction "1_2") (pintype "passive"))
      (node (ref "R49") (pin "1") (pinfunction "2_1") (pintype "passive"))
    )
    (net (code "144") (name "Net-(C38-Pad2)") (class "Default")
      (node (ref "C38") (pin "2") (pinfunction "2_2") (pintype "passive"))
      (node (ref "R25") (pin "S") (pinfunction "S_S") (pintype "passive"))
    )
    (net (code "145") (name "Net-(C46-Pad2)") (class "Default")
      (node (ref "C46") (pin "2") (pinfunction "2_2") (pintype "passive"))
      (node (ref "R18") (pin "S") (pinfunction "S_S") (pintype "passive"))
    )
    (net (code "146") (name "Net-(C66-Pad1)") (class "Default")
      (node (ref "C66") (pin "1") (pinfunction "1_1") (pintype "passive"))
      (node (ref "D1") (pin "C") (pinfunction "C_C") (pintype "passive"))
      (node (ref "D2") (pin "A") (pinfunction "A_A") (pintype "passive"))
    )
    (net (code "147") (name "Net-(C67-Pad1)") (class "Default")
      (node (ref "C67") (pin "1") (pinfunction "1_1") (pintype "passive"))
      (node (ref "D3") (pin "A") (pinfunction "A_A") (pintype "passive"))
      (node (ref "D4") (pin "C") (pinfunction "C_C") (pintype "passive"))
    )
    (net (code "148") (name "Net-(D6-C)") (class "Default")
      (node (ref "D6") (pin "K") (pinfunction "C_K") (pintype "passive"))
      (node (ref "R46") (pin "1") (pinfunction "2_1") (pintype "passive"))
    )
    (net (code "149") (name "Net-(D7-C)") (class "Default")
      (node (ref "D7") (pin "K") (pinfunction "C_K") (pintype "passive"))
      (node (ref "R47") (pin "1") (pinfunction "2_1") (pintype "passive"))
    )
    (net (code "150") (name "Net-(D8-C)") (class "Default")
      (node (ref "D8") (pin "K") (pinfunction "C_K") (pintype "passive"))
      (node (ref "R48") (pin "1") (pinfunction "2_1") (pintype "passive"))
    )
    (net (code "151") (name "Net-(L1-C)") (class "Default")
      (node (ref "L1") (pin "K") (pinfunction "C_K") (pintype "passive"))
      (node (ref "L2") (pin "A") (pinfunction "A_A") (pintype "passive"))
    )
    (net (code "152") (name "Net-(L2-C)") (class "Default")
      (node (ref "L2") (pin "K") (pinfunction "C_K") (pintype "passive"))
      (node (ref "L3") (pin "A") (pinfunction "A_A") (pintype "passive"))
    )
    (net (code "153") (name "Net-(L4-C)") (class "Default")
      (node (ref "L4") (pin "K") (pinfunction "C_K") (pintype "passive"))
      (node (ref "L5") (pin "A") (pinfunction "A_A") (pintype "passive"))
    )
    (net (code "154") (name "Net-(L5-C)") (class "Default")
      (node (ref "L5") (pin "K") (pinfunction "C_K") (pintype "passive"))
      (node (ref "L6") (pin "A") (pinfunction "A_A") (pintype "passive"))
    )
    (net (code "155") (name "Net-(L7-C)") (class "Default")
      (node (ref "L7") (pin "K") (pinfunction "C_K") (pintype "passive"))
      (node (ref "L8") (pin "A") (pinfunction "A_A") (pintype "passive"))
    )
    (net (code "156") (name "Net-(L8-C)") (class "Default")
      (node (ref "L8") (pin "K") (pinfunction "C_K") (pintype "passive"))
      (node (ref "L9") (pin "A") (pinfunction "A_A") (pintype "passive"))
    )
    (net (code "157") (name "Net-(L10-C)") (class "Default")
      (node (ref "L10") (pin "K") (pinfunction "C_K") (pintype "passive"))
      (node (ref "L11") (pin "A") (pinfunction "A_A") (pintype "passive"))
    )
    (net (code "158") (name "Net-(L11-C)") (class "Default")
      (node (ref "L11") (pin "K") (pinfunction "C_K") (pintype "passive"))
      (node (ref "L12") (pin "A") (pinfunction "A_A") (pintype "passive"))
    )
    (net (code "159") (name "Net-(OK1-A)") (class "Default")
      (node (ref "D5") (pin "C") (pinfunction "C_C") (pintype "passive"))
      (node (ref "OK1") (pin "1") (pinfunction "A_1") (pintype "passive"))
      (node (ref "R61") (pin "1") (pinfunction "2_1") (pintype "passive"))
    )
    (net (code "160") (name "Net-(OK1-C)") (class "Default")
      (node (ref "D5") (pin "A") (pinfunction "A_A") (pintype "passive"))
      (node (ref "M1") (pin "5") (pinfunction "5_5") (pintype "passive"))
      (node (ref "OK1") (pin "2") (pinfunction "C_2") (pintype "passive"))
    )
    (net (code "161") (name "Net-(R19-2)") (class "Default")
      (node (ref "R19") (pin "1") (pinfunction "2_1") (pintype "passive"))
      (node (ref "R25") (pin "A") (pinfunction "A_A") (pintype "passive"))
      (node (ref "R26") (pin "2") (pinfunction "1_2") (pintype "passive"))
      (node (ref "R35") (pin "1") (pinfunction "2_1") (pintype "passive"))
      (node (ref "R42") (pin "1") (pinfunction "2_1") (pintype "passive"))
      (node (ref "R62") (pin "1") (pinfunction "2_1") (pintype "passive"))
    )
    (net (code "162") (name "Net-(R20-1)") (class "Default")
      (node (ref "R18") (pin "A") (pinfunction "A_A") (pintype "passive"))
      (node (ref "R20") (pin "2") (pinfunction "1_2") (pintype "passive"))
      (node (ref "R24") (pin "1") (pinfunction "2_1") (pintype "passive"))
      (node (ref "R36") (pin "1") (pinfunction "2_1") (pintype "passive"))
      (node (ref "R44") (pin "1") (pinfunction "2_1") (pintype "passive"))
      (node (ref "R66") (pin "1") (pinfunction "2_1") (pintype "passive"))
    )
    (net (code "163") (name "Net-(R20-2)") (class "Default")
      (node (ref "C44") (pin "2") (pinfunction "2_2") (pintype "passive"))
      (node (ref "R20") (pin "1") (pinfunction "2_1") (pintype "passive"))
      (node (ref "R22") (pin "2") (pinfunction "1_2") (pintype "passive"))
    )
    (net (code "164") (name "Net-(R21-2)") (class "Default")
      (node (ref "C40") (pin "+") (pinfunction "+_+") (pintype "passive"))
      (node (ref "R21") (pin "1") (pinfunction "2_1") (pintype "passive"))
    )
    (net (code "165") (name "Net-(R23-2)") (class "Default")
      (node (ref "C40") (pin "-") (pinfunction "-_-") (pintype "passive"))
      (node (ref "R23") (pin "1") (pinfunction "2_1") (pintype "passive"))
      (node (ref "X1") (pin "5") (pinfunction "5_5") (pintype "passive"))
    )
    (net (code "166") (name "Net-(R26-2)") (class "Default")
      (node (ref "C48") (pin "2") (pinfunction "2_2") (pintype "passive"))
      (node (ref "R26") (pin "1") (pinfunction "2_1") (pintype "passive"))
      (node (ref "R27") (pin "2") (pinfunction "1_2") (pintype "passive"))
    )
    (net (code "167") (name "Net-(R28-2)") (class "Default")
      (node (ref "C47") (pin "+") (pinfunction "+_+") (pintype "passive"))
      (node (ref "R28") (pin "1") (pinfunction "2_1") (pintype "passive"))
    )
    (net (code "168") (name "Net-(R29-2)") (class "Default")
      (node (ref "C47") (pin "-") (pinfunction "-_-") (pintype "passive"))
      (node (ref "R29") (pin "1") (pinfunction "2_1") (pintype "passive"))
      (node (ref "X1") (pin "2") (pinfunction "2_2") (pintype "passive"))
    )
    (net (code "169") (name "Net-(R30-1)") (class "Default")
      (node (ref "L1") (pin "A") (pinfunction "A_A") (pintype "passive"))
      (node (ref "R30") (pin "2") (pinfunction "1_2") (pintype "passive"))
    )
    (net (code "170") (name "Net-(R31-1)") (class "Default")
      (node (ref "L4") (pin "A") (pinfunction "A_A") (pintype "passive"))
      (node (ref "R31") (pin "2") (pinfunction "1_2") (pintype "passive"))
    )
    (net (code "171") (name "Net-(R32-1)") (class "Default")
      (node (ref "L7") (pin "A") (pinfunction "A_A") (pintype "passive"))
      (node (ref "R32") (pin "2") (pinfunction "1_2") (pintype "passive"))
    )
    (net (code "172") (name "Net-(R33-1)") (class "Default")
      (node (ref "L10") (pin "A") (pinfunction "A_A") (pintype "passive"))
      (node (ref "R33") (pin "2") (pinfunction "1_2") (pintype "passive"))
    )
    (net (code "173") (name "Net-(R55-1)") (class "Default")
      (node (ref "D9") (pin "A") (pinfunction "A_A") (pintype "passive"))
      (node (ref "R55") (pin "2") (pinfunction "1_2") (pintype "passive"))
    )
    (net (code "174") (name "Net-(R60-1)") (class "Default")
      (node (ref "C75") (pin "2") (pinfunction "2_2") (pintype "passive"))
      (node (ref "Q13") (pin "2") (pinfunction "2_2") (pintype "passive"))
      (node (ref "R60") (pin "2") (pinfunction "1_2") (pintype "passive"))
    )
    (net (code "175") (name "Net-(R61-1)") (class "Default")
      (node (ref "M1") (pin "4") (pinfunction "4_4") (pintype "passive"))
      (node (ref "R61") (pin "2") (pinfunction "1_2") (pintype "passive"))
    )
    (net (code "176") (name "Net-(R77-2)") (class "Default")
      (node (ref "M2") (pin "4") (pinfunction "4_4") (pintype "passive"))
      (node (ref "R77") (pin "1") (pinfunction "2_1") (pintype "passive"))
    )
    (net (code "177") (name "Net-(R78-2)") (class "Default")
      (node (ref "M2") (pin "5") (pinfunction "5_5") (pintype "passive"))
      (node (ref "R78") (pin "1") (pinfunction "2_1") (pintype "passive"))
    )
    (net (code "178") (name "RX") (class "Default")
      (node (ref "A1") (pin "2") (pinfunction "GP1_2") (pintype "bidirectional"))
      (node (ref "A2") (pin "6") (pinfunction "O_6") (pintype "output"))
    )
    (net (code "179") (name "SHIFT") (class "Default")
      (node (ref "A1") (pin "24") (pinfunction "GP18_24") (pintype "bidirectional"))
      (node (ref "A14") (pin "11") (pinfunction "SCK_11") (pintype "input"))
      (node (ref "A6") (pin "11") (pinfunction "SCK_11") (pintype "input"))
    )
    (net (code "180") (name "SPI0-CS1") (class "Default")
      (node (ref "A1") (pin "7") (pinfunction "GP5_7") (pintype "bidirectional"))
      (node (ref "A23") (pin "15") (pinfunction "INH_15") (pintype "input"))
      (node (ref "A24") (pin "15") (pinfunction "INH_15") (pintype "input"))
    )
    (net (code "181") (name "SPI0-CS2") (class "Default")
      (node (ref "A1") (pin "26") (pinfunction "GP20_26") (pintype "bidirectional"))
      (node (ref "JP4") (pin "5") (pinfunction "5_5") (pintype "passive"))
    )
    (net (code "182") (name "SPI0-CS3") (class "Default")
      (node (ref "A1") (pin "27") (pinfunction "GP21_27") (pintype "bidirectional"))
      (node (ref "JP3") (pin "5") (pinfunction "5_5") (pintype "passive"))
    )
    (net (code "183") (name "SPI0-CS4") (class "Default")
      (node (ref "A1") (pin "29") (pinfunction "GP22_29") (pintype "bidirectional"))
      (node (ref "JP2") (pin "5") (pinfunction "5_5") (pintype "passive"))
    )
    (net (code "184") (name "SPI0-RX") (class "Default")
      (node (ref "A1") (pin "6") (pinfunction "GP4_6") (pintype "bidirectional"))
      (node (ref "A24") (pin "9") (pinfunction "QH_9") (pintype "output"))
      (node (ref "JP2") (pin "2") (pinfunction "2_2") (pintype "passive"))
      (node (ref "JP3") (pin "2") (pinfunction "2_2") (pintype "passive"))
      (node (ref "JP4") (pin "2") (pinfunction "2_2") (pintype "passive"))
    )
    (net (code "185") (name "SPI0-SCK") (class "Default")
      (node (ref "A1") (pin "4") (pinfunction "GP2_4") (pintype "bidirectional"))
      (node (ref "A23") (pin "2") (pinfunction "CLK_2") (pintype "input"))
      (node (ref "A24") (pin "2") (pinfunction "CLK_2") (pintype "input"))
      (node (ref "JP2") (pin "4") (pinfunction "4_4") (pintype "passive"))
      (node (ref "JP3") (pin "4") (pinfunction "4_4") (pintype "passive"))
      (node (ref "JP4") (pin "4") (pinfunction "4_4") (pintype "passive"))
    )
    (net (code "186") (name "SPI0-TX") (class "Default")
      (node (ref "A1") (pin "5") (pinfunction "GP3_5") (pintype "bidirectional"))
      (node (ref "JP2") (pin "3") (pinfunction "3_3") (pintype "passive"))
      (node (ref "JP3") (pin "3") (pinfunction "3_3") (pintype "passive"))
      (node (ref "JP4") (pin "3") (pinfunction "3_3") (pintype "passive"))
    )
    (net (code "187") (name "TX") (class "Default")
      (node (ref "A1") (pin "1") (pinfunction "GP0_1") (pintype "bidirectional"))
      (node (ref "A2") (pin "1") (pinfunction "I_1") (pintype "input"))
    )
    (net (code "188") (name "unconnected-(A1-3V3_EN-Pad37)") (class "Default")
      (node (ref "A1") (pin "37") (pinfunction "3V3_EN_37") (pintype "bidirectional"))
    )
    (net (code "189") (name "unconnected-(A1-BOOTSEL-PadTP6)") (class "Default")
      (node (ref "A1") (pin "TP6") (pinfunction "BOOTSEL_TP6") (pintype "bidirectional"))
    )
    (net (code "190") (name "unconnected-(A1-GPIO23{slash}SMPS_PS_PIN_(DO_NOT_USE)-PadTP4)") (class "Default")
      (node (ref "A1") (pin "TP4") (pinfunction "GPIO23/SMPS_PS_PIN_(DO_NOT_USE)_TP4") (pintype "bidirectional"))
    )
    (net (code "191") (name "unconnected-(A1-GPIO25{slash}LED_(NOT_RECOMMENDED_TO_BE_USED)-PadTP5)") (class "Default")
      (node (ref "A1") (pin "TP5") (pinfunction "GPIO25/LED_(NOT_RECOMMENDED_TO_BE_USED)_TP5") (pintype "bidirectional"))
    )
    (net (code "192") (name "unconnected-(A1-PadMH1)") (class "Default")
      (node (ref "A1") (pin "MH1") (pinfunction "MH1_MH1") (pintype "bidirectional"))
    )
    (net (code "193") (name "unconnected-(A1-PadMH2)") (class "Default")
      (node (ref "A1") (pin "MH2") (pinfunction "MH2_MH2") (pintype "bidirectional"))
    )
    (net (code "194") (name "unconnected-(A1-PadMH3)") (class "Default")
      (node (ref "A1") (pin "MH3") (pinfunction "MH3_MH3") (pintype "bidirectional"))
    )
    (net (code "195") (name "unconnected-(A1-PadMH4)") (class "Default")
      (node (ref "A1") (pin "MH4") (pinfunction "MH4_MH4") (pintype "bidirectional"))
    )
    (net (code "196") (name "unconnected-(A1-RUN-Pad30)") (class "Default")
      (node (ref "A1") (pin "30") (pinfunction "RUN_30") (pintype "bidirectional"))
    )
    (net (code "197") (name "unconnected-(A1-SWCLK-PadD1)") (class "Default")
      (node (ref "A1") (pin "D1") (pinfunction "SWCLK_D1") (pintype "bidirectional"))
    )
    (net (code "198") (name "unconnected-(A1-SWDIO-PadD3)") (class "Default")
      (node (ref "A1") (pin "D3") (pinfunction "SWDIO_D3") (pintype "bidirectional"))
    )
    (net (code "199") (name "unconnected-(A1-USB_DM-PadTP2)") (class "Default")
      (node (ref "A1") (pin "TP2") (pinfunction "USB_DM_TP2") (pintype "bidirectional"))
    )
    (net (code "200") (name "unconnected-(A1-USB_DP-PadTP3)") (class "Default")
      (node (ref "A1") (pin "TP3") (pinfunction "USB_DP_TP3") (pintype "bidirectional"))
    )
    (net (code "201") (name "unconnected-(A1-VBUS-Pad40)") (class "Default")
      (node (ref "A1") (pin "40") (pinfunction "VBUS_40") (pintype "bidirectional"))
    )
    (net (code "202") (name "unconnected-(A6A-QH*-Pad9)") (class "Default")
      (node (ref "A6") (pin "9") (pinfunction "QH*_9") (pintype "tri_state"))
    )
    (net (code "203") (name "unconnected-(A7-TEST-Pad9)") (class "Default")
      (node (ref "A7") (pin "9") (pinfunction "TEST_9") (pintype "bidirectional"))
    )
    (net (code "204") (name "unconnected-(A7-~{IRQ}-Pad2)") (class "Default")
      (node (ref "A7") (pin "2") (pinfunction "~{IRQ}_2") (pintype "bidirectional"))
    )
    (net (code "205") (name "unconnected-(A8-TST2-Pad15)") (class "Default")
      (node (ref "A8") (pin "15") (pinfunction "TST2_15") (pintype "bidirectional"))
    )
    (net (code "206") (name "unconnected-(A9-TST2-Pad15)") (class "Default")
      (node (ref "A9") (pin "15") (pinfunction "TST2_15") (pintype "bidirectional"))
    )
    (net (code "207") (name "unconnected-(A15-TEST-Pad9)") (class "Default")
      (node (ref "A15") (pin "9") (pinfunction "TEST_9") (pintype "bidirectional"))
    )
    (net (code "208") (name "unconnected-(A15-~{IRQ}-Pad2)") (class "Default")
      (node (ref "A15") (pin "2") (pinfunction "~{IRQ}_2") (pintype "bidirectional"))
    )
    (net (code "209") (name "unconnected-(A16-TST2-Pad15)") (class "Default")
      (node (ref "A16") (pin "15") (pinfunction "TST2_15") (pintype "bidirectional"))
    )
    (net (code "210") (name "unconnected-(A17-TST2-Pad15)") (class "Default")
      (node (ref "A17") (pin "15") (pinfunction "TST2_15") (pintype "bidirectional"))
    )
    (net (code "211") (name "unconnected-(A23A-~{QH}-Pad7)") (class "Default")
      (node (ref "A23") (pin "7") (pinfunction "~{QH}_7") (pintype "output"))
    )
    (net (code "212") (name "unconnected-(A24A-~{QH}-Pad7)") (class "Default")
      (node (ref "A24") (pin "7") (pinfunction "~{QH}_7") (pintype "output"))
    )
    (net (code "213") (name "unconnected-(A28B-OUT-Pad7)") (class "Default")
      (node (ref "A28") (pin "7") (pinfunction "OUT_7") (pintype "output"))
    )
    (net (code "214") (name "unconnected-(J2-Pad2)") (class "Default")
      (node (ref "J2") (pin "2") (pinfunction "2_2") (pintype "passive"))
    )
    (net (code "215") (name "unconnected-(M1-Pad1)") (class "Default")
      (node (ref "M1") (pin "1") (pinfunction "1_1") (pintype "passive"))
    )
    (net (code "216") (name "unconnected-(M1-Pad2)") (class "Default")
      (node (ref "M1") (pin "2") (pinfunction "2_2") (pintype "passive"))
    )
    (net (code "217") (name "unconnected-(M1-Pad3)") (class "Default")
      (node (ref "M1") (pin "3") (pinfunction "3_3") (pintype "passive"))
    )
    (net (code "218") (name "unconnected-(M2-Pad1)") (class "Default")
      (node (ref "M2") (pin "1") (pinfunction "1_1") (pintype "passive"))
    )
    (net (code "219") (name "unconnected-(M2-Pad3)") (class "Default")
      (node (ref "M2") (pin "3") (pinfunction "3_3") (pintype "passive"))
    )
    (net (code "220") (name "unconnected-(R18-PadE)") (class "Default")
      (node (ref "R18") (pin "E") (pinfunction "E_E") (pintype "passive"))
    )
    (net (code "221") (name "unconnected-(R25-PadE)") (class "Default")
      (node (ref "R25") (pin "E") (pinfunction "E_E") (pintype "passive"))
    )
    (net (code "222") (name "unconnected-(S1-COM1-PadT4)") (class "Default")
      (node (ref "S1") (pin "T4") (pinfunction "COM1_T4") (pintype "bidirectional"))
    )
    (net (code "223") (name "unconnected-(S1-NO2-PadT1)") (class "Default")
      (node (ref "S1") (pin "T1") (pinfunction "NO2_T1") (pintype "bidirectional"))
    )
    (net (code "224") (name "unconnected-(S2-COM1-PadT4)") (class "Default")
      (node (ref "S2") (pin "T4") (pinfunction "COM1_T4") (pintype "bidirectional"))
    )
    (net (code "225") (name "unconnected-(S2-NO2-PadT1)") (class "Default")
      (node (ref "S2") (pin "T1") (pinfunction "NO2_T1") (pintype "bidirectional"))
    )
    (net (code "226") (name "unconnected-(S3-COM1-PadT4)") (class "Default")
      (node (ref "S3") (pin "T4") (pinfunction "COM1_T4") (pintype "bidirectional"))
    )
    (net (code "227") (name "unconnected-(S3-NO2-PadT1)") (class "Default")
      (node (ref "S3") (pin "T1") (pinfunction "NO2_T1") (pintype "bidirectional"))
    )
    (net (code "228") (name "unconnected-(S4-COM1-PadT4)") (class "Default")
      (node (ref "S4") (pin "T4") (pinfunction "COM1_T4") (pintype "bidirectional"))
    )
    (net (code "229") (name "unconnected-(S4-NO2-PadT1)") (class "Default")
      (node (ref "S4") (pin "T1") (pinfunction "NO2_T1") (pintype "bidirectional"))
    )
    (net (code "230") (name "unconnected-(S5-COM1-PadT4)") (class "Default")
      (node (ref "S5") (pin "T4") (pinfunction "COM1_T4") (pintype "bidirectional"))
    )
    (net (code "231") (name "unconnected-(S5-NO2-PadT1)") (class "Default")
      (node (ref "S5") (pin "T1") (pinfunction "NO2_T1") (pintype "bidirectional"))
    )
    (net (code "232") (name "unconnected-(S6-COM1-PadT4)") (class "Default")
      (node (ref "S6") (pin "T4") (pinfunction "COM1_T4") (pintype "bidirectional"))
    )
    (net (code "233") (name "unconnected-(S6-NO2-PadT1)") (class "Default")
      (node (ref "S6") (pin "T1") (pinfunction "NO2_T1") (pintype "bidirectional"))
    )
    (net (code "234") (name "unconnected-(S7-COM1-PadT4)") (class "Default")
      (node (ref "S7") (pin "T4") (pinfunction "COM1_T4") (pintype "bidirectional"))
    )
    (net (code "235") (name "unconnected-(S7-NO2-PadT1)") (class "Default")
      (node (ref "S7") (pin "T1") (pinfunction "NO2_T1") (pintype "bidirectional"))
    )
    (net (code "236") (name "unconnected-(S8-COM1-PadT4)") (class "Default")
      (node (ref "S8") (pin "T4") (pinfunction "COM1_T4") (pintype "bidirectional"))
    )
    (net (code "237") (name "unconnected-(S8-NO2-PadT1)") (class "Default")
      (node (ref "S8") (pin "T1") (pinfunction "NO2_T1") (pintype "bidirectional"))
    )
    (net (code "238") (name "unconnected-(S9-COM1-PadT4)") (class "Default")
      (node (ref "S9") (pin "T4") (pinfunction "COM1_T4") (pintype "bidirectional"))
    )
    (net (code "239") (name "unconnected-(S9-NO2-PadT1)") (class "Default")
      (node (ref "S9") (pin "T1") (pinfunction "NO2_T1") (pintype "bidirectional"))
    )
    (net (code "240") (name "unconnected-(S10-COM1-PadT4)") (class "Default")
      (node (ref "S10") (pin "T4") (pinfunction "COM1_T4") (pintype "bidirectional"))
    )
    (net (code "241") (name "unconnected-(S10-NO2-PadT1)") (class "Default")
      (node (ref "S10") (pin "T1") (pinfunction "NO2_T1") (pintype "bidirectional"))
    )
    (net (code "242") (name "unconnected-(S11-COM1-PadT4)") (class "Default")
      (node (ref "S11") (pin "T4") (pinfunction "COM1_T4") (pintype "bidirectional"))
    )
    (net (code "243") (name "unconnected-(S11-NO2-PadT1)") (class "Default")
      (node (ref "S11") (pin "T1") (pinfunction "NO2_T1") (pintype "bidirectional"))
    )
    (net (code "244") (name "unconnected-(S12-COM1-PadT4)") (class "Default")
      (node (ref "S12") (pin "T4") (pinfunction "COM1_T4") (pintype "bidirectional"))
    )
    (net (code "245") (name "unconnected-(S12-NO2-PadT1)") (class "Default")
      (node (ref "S12") (pin "T1") (pinfunction "NO2_T1") (pintype "bidirectional"))
    )
    (net (code "246") (name "unconnected-(S13-COM1-PadT4)") (class "Default")
      (node (ref "S13") (pin "T4") (pinfunction "COM1_T4") (pintype "bidirectional"))
    )
    (net (code "247") (name "unconnected-(S13-NO2-PadT1)") (class "Default")
      (node (ref "S13") (pin "T1") (pinfunction "NO2_T1") (pintype "bidirectional"))
    )
    (net (code "248") (name "unconnected-(S14-COM1-PadT4)") (class "Default")
      (node (ref "S14") (pin "T4") (pinfunction "COM1_T4") (pintype "bidirectional"))
    )
    (net (code "249") (name "unconnected-(S14-NO2-PadT1)") (class "Default")
      (node (ref "S14") (pin "T1") (pinfunction "NO2_T1") (pintype "bidirectional"))
    )
    (net (code "250") (name "unconnected-(S15-COM1-PadT4)") (class "Default")
      (node (ref "S15") (pin "T4") (pinfunction "COM1_T4") (pintype "bidirectional"))
    )
    (net (code "251") (name "unconnected-(S15-NO2-PadT1)") (class "Default")
      (node (ref "S15") (pin "T1") (pinfunction "NO2_T1") (pintype "bidirectional"))
    )
    (net (code "252") (name "unconnected-(S16-COM1-PadT4)") (class "Default")
      (node (ref "S16") (pin "T4") (pinfunction "COM1_T4") (pintype "bidirectional"))
    )
    (net (code "253") (name "unconnected-(S16-NO2-PadT1)") (class "Default")
      (node (ref "S16") (pin "T1") (pinfunction "NO2_T1") (pintype "bidirectional"))
    )
    (net (code "254") (name "unconnected-(X1-Pad3)") (class "Default")
      (node (ref "X1") (pin "3") (pinfunction "3_3") (pintype "passive"))
    )
    (net (code "255") (name "unconnected-(X1-Pad4)") (class "Default")
      (node (ref "X1") (pin "4") (pinfunction "4_4") (pintype "passive"))
    )
  )
)
